# PCB_v1.net
KiCad netlist of a schematic drawn in EAGLE
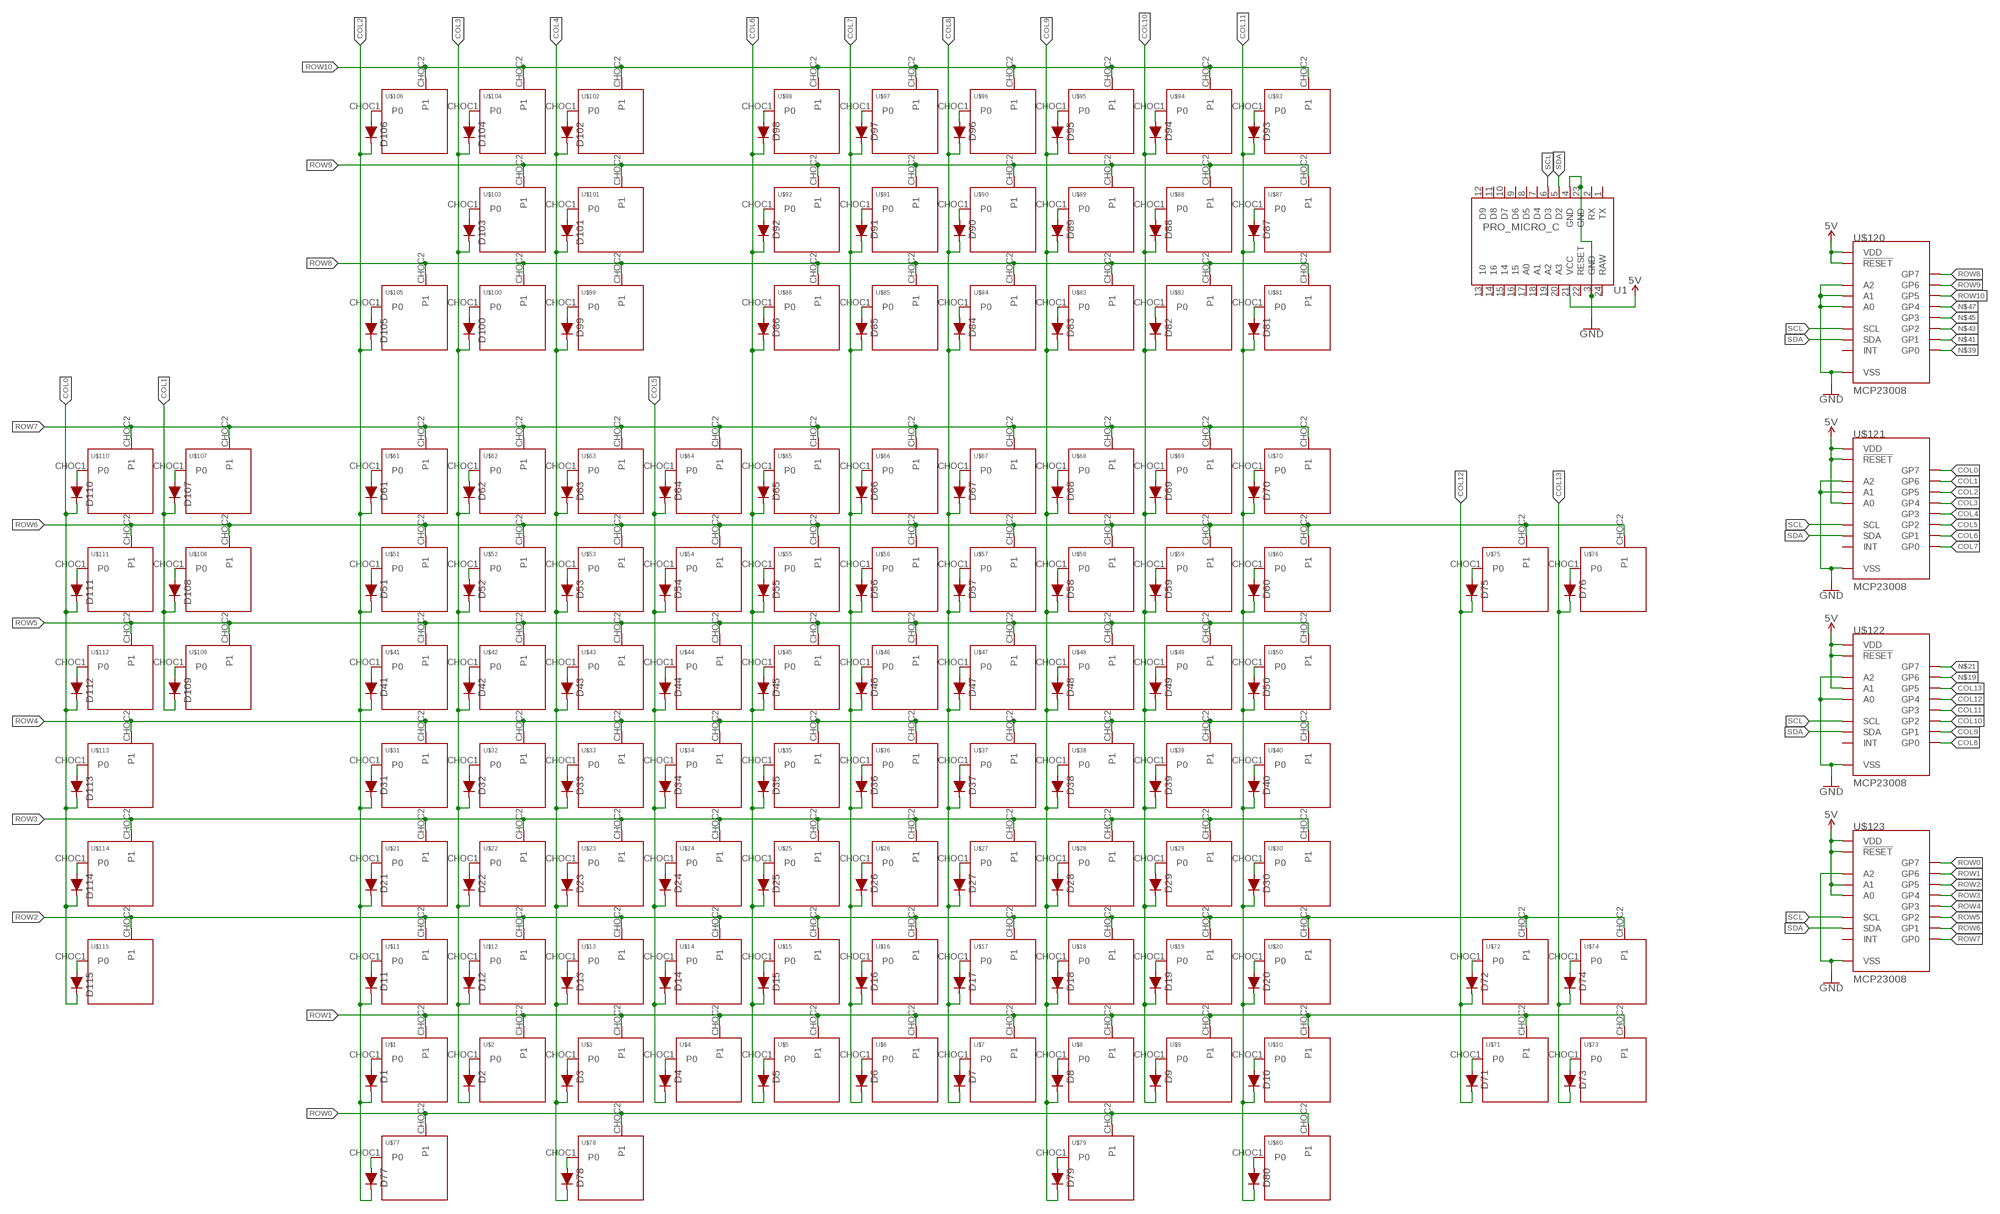
[diagram p0: schematic, sheet 1]

(export (version "E")
  (design (tool "Eeschema 10.0.6"))
  (components
    (comp (ref "D1")
      (value "200mA/100V/1V")
      (footprint "eagle-import:DIODE-1N4148-KIT")
      (libsource (lib "eagle-import") (part "DIODE-KIT"))
    )
    (comp (ref "D2")
      (value "200mA/100V/1V")
      (footprint "eagle-import:DIODE-1N4148-KIT")
      (libsource (lib "eagle-import") (part "DIODE-KIT"))
    )
    (comp (ref "D3")
      (value "200mA/100V/1V")
      (footprint "eagle-import:DIODE-1N4148-KIT")
      (libsource (lib "eagle-import") (part "DIODE-KIT"))
    )
    (comp (ref "D4")
      (value "200mA/100V/1V")
      (footprint "eagle-import:DIODE-1N4148-KIT")
      (libsource (lib "eagle-import") (part "DIODE-KIT"))
    )
    (comp (ref "D5")
      (value "200mA/100V/1V")
      (footprint "eagle-import:DIODE-1N4148-KIT")
      (libsource (lib "eagle-import") (part "DIODE-KIT"))
    )
    (comp (ref "D6")
      (value "200mA/100V/1V")
      (footprint "eagle-import:DIODE-1N4148-KIT")
      (libsource (lib "eagle-import") (part "DIODE-KIT"))
    )
    (comp (ref "D7")
      (value "200mA/100V/1V")
      (footprint "eagle-import:DIODE-1N4148-KIT")
      (libsource (lib "eagle-import") (part "DIODE-KIT"))
    )
    (comp (ref "D8")
      (value "200mA/100V/1V")
      (footprint "eagle-import:DIODE-1N4148-KIT")
      (libsource (lib "eagle-import") (part "DIODE-KIT"))
    )
    (comp (ref "D9")
      (value "200mA/100V/1V")
      (footprint "eagle-import:DIODE-1N4148-KIT")
      (libsource (lib "eagle-import") (part "DIODE-KIT"))
    )
    (comp (ref "D10")
      (value "200mA/100V/1V")
      (footprint "eagle-import:DIODE-1N4148-KIT")
      (libsource (lib "eagle-import") (part "DIODE-KIT"))
    )
    (comp (ref "D11")
      (value "200mA/100V/1V")
      (footprint "eagle-import:DIODE-1N4148-KIT")
      (libsource (lib "eagle-import") (part "DIODE-KIT"))
    )
    (comp (ref "D12")
      (value "200mA/100V/1V")
      (footprint "eagle-import:DIODE-1N4148-KIT")
      (libsource (lib "eagle-import") (part "DIODE-KIT"))
    )
    (comp (ref "D13")
      (value "200mA/100V/1V")
      (footprint "eagle-import:DIODE-1N4148-KIT")
      (libsource (lib "eagle-import") (part "DIODE-KIT"))
    )
    (comp (ref "D14")
      (value "200mA/100V/1V")
      (footprint "eagle-import:DIODE-1N4148-KIT")
      (libsource (lib "eagle-import") (part "DIODE-KIT"))
    )
    (comp (ref "D15")
      (value "200mA/100V/1V")
      (footprint "eagle-import:DIODE-1N4148-KIT")
      (libsource (lib "eagle-import") (part "DIODE-KIT"))
    )
    (comp (ref "D16")
      (value "200mA/100V/1V")
      (footprint "eagle-import:DIODE-1N4148-KIT")
      (libsource (lib "eagle-import") (part "DIODE-KIT"))
    )
    (comp (ref "D17")
      (value "200mA/100V/1V")
      (footprint "eagle-import:DIODE-1N4148-KIT")
      (libsource (lib "eagle-import") (part "DIODE-KIT"))
    )
    (comp (ref "D18")
      (value "200mA/100V/1V")
      (footprint "eagle-import:DIODE-1N4148-KIT")
      (libsource (lib "eagle-import") (part "DIODE-KIT"))
    )
    (comp (ref "D19")
      (value "200mA/100V/1V")
      (footprint "eagle-import:DIODE-1N4148-KIT")
      (libsource (lib "eagle-import") (part "DIODE-KIT"))
    )
    (comp (ref "D20")
      (value "200mA/100V/1V")
      (footprint "eagle-import:DIODE-1N4148-KIT")
      (libsource (lib "eagle-import") (part "DIODE-KIT"))
    )
    (comp (ref "D21")
      (value "200mA/100V/1V")
      (footprint "eagle-import:DIODE-1N4148-KIT")
      (libsource (lib "eagle-import") (part "DIODE-KIT"))
    )
    (comp (ref "D22")
      (value "200mA/100V/1V")
      (footprint "eagle-import:DIODE-1N4148-KIT")
      (libsource (lib "eagle-import") (part "DIODE-KIT"))
    )
    (comp (ref "D23")
      (value "200mA/100V/1V")
      (footprint "eagle-import:DIODE-1N4148-KIT")
      (libsource (lib "eagle-import") (part "DIODE-KIT"))
    )
    (comp (ref "D24")
      (value "200mA/100V/1V")
      (footprint "eagle-import:DIODE-1N4148-KIT")
      (libsource (lib "eagle-import") (part "DIODE-KIT"))
    )
    (comp (ref "D25")
      (value "200mA/100V/1V")
      (footprint "eagle-import:DIODE-1N4148-KIT")
      (libsource (lib "eagle-import") (part "DIODE-KIT"))
    )
    (comp (ref "D26")
      (value "200mA/100V/1V")
      (footprint "eagle-import:DIODE-1N4148-KIT")
      (libsource (lib "eagle-import") (part "DIODE-KIT"))
    )
    (comp (ref "D27")
      (value "200mA/100V/1V")
      (footprint "eagle-import:DIODE-1N4148-KIT")
      (libsource (lib "eagle-import") (part "DIODE-KIT"))
    )
    (comp (ref "D28")
      (value "200mA/100V/1V")
      (footprint "eagle-import:DIODE-1N4148-KIT")
      (libsource (lib "eagle-import") (part "DIODE-KIT"))
    )
    (comp (ref "D29")
      (value "200mA/100V/1V")
      (footprint "eagle-import:DIODE-1N4148-KIT")
      (libsource (lib "eagle-import") (part "DIODE-KIT"))
    )
    (comp (ref "D30")
      (value "200mA/100V/1V")
      (footprint "eagle-import:DIODE-1N4148-KIT")
      (libsource (lib "eagle-import") (part "DIODE-KIT"))
    )
    (comp (ref "D31")
      (value "200mA/100V/1V")
      (footprint "eagle-import:DIODE-1N4148-KIT")
      (libsource (lib "eagle-import") (part "DIODE-KIT"))
    )
    (comp (ref "D32")
      (value "200mA/100V/1V")
      (footprint "eagle-import:DIODE-1N4148-KIT")
      (libsource (lib "eagle-import") (part "DIODE-KIT"))
    )
    (comp (ref "D33")
      (value "200mA/100V/1V")
      (footprint "eagle-import:DIODE-1N4148-KIT")
      (libsource (lib "eagle-import") (part "DIODE-KIT"))
    )
    (comp (ref "D34")
      (value "200mA/100V/1V")
      (footprint "eagle-import:DIODE-1N4148-KIT")
      (libsource (lib "eagle-import") (part "DIODE-KIT"))
    )
    (comp (ref "D35")
      (value "200mA/100V/1V")
      (footprint "eagle-import:DIODE-1N4148-KIT")
      (libsource (lib "eagle-import") (part "DIODE-KIT"))
    )
    (comp (ref "D36")
      (value "200mA/100V/1V")
      (footprint "eagle-import:DIODE-1N4148-KIT")
      (libsource (lib "eagle-import") (part "DIODE-KIT"))
    )
    (comp (ref "D37")
      (value "200mA/100V/1V")
      (footprint "eagle-import:DIODE-1N4148-KIT")
      (libsource (lib "eagle-import") (part "DIODE-KIT"))
    )
    (comp (ref "D38")
      (value "200mA/100V/1V")
      (footprint "eagle-import:DIODE-1N4148-KIT")
      (libsource (lib "eagle-import") (part "DIODE-KIT"))
    )
    (comp (ref "D39")
      (value "200mA/100V/1V")
      (footprint "eagle-import:DIODE-1N4148-KIT")
      (libsource (lib "eagle-import") (part "DIODE-KIT"))
    )
    (comp (ref "D40")
      (value "200mA/100V/1V")
      (footprint "eagle-import:DIODE-1N4148-KIT")
      (libsource (lib "eagle-import") (part "DIODE-KIT"))
    )
    (comp (ref "D41")
      (value "200mA/100V/1V")
      (footprint "eagle-import:DIODE-1N4148-KIT")
      (libsource (lib "eagle-import") (part "DIODE-KIT"))
    )
    (comp (ref "D42")
      (value "200mA/100V/1V")
      (footprint "eagle-import:DIODE-1N4148-KIT")
      (libsource (lib "eagle-import") (part "DIODE-KIT"))
    )
    (comp (ref "D43")
      (value "200mA/100V/1V")
      (footprint "eagle-import:DIODE-1N4148-KIT")
      (libsource (lib "eagle-import") (part "DIODE-KIT"))
    )
    (comp (ref "D44")
      (value "200mA/100V/1V")
      (footprint "eagle-import:DIODE-1N4148-KIT")
      (libsource (lib "eagle-import") (part "DIODE-KIT"))
    )
    (comp (ref "D45")
      (value "200mA/100V/1V")
      (footprint "eagle-import:DIODE-1N4148-KIT")
      (libsource (lib "eagle-import") (part "DIODE-KIT"))
    )
    (comp (ref "D46")
      (value "200mA/100V/1V")
      (footprint "eagle-import:DIODE-1N4148-KIT")
      (libsource (lib "eagle-import") (part "DIODE-KIT"))
    )
    (comp (ref "D47")
      (value "200mA/100V/1V")
      (footprint "eagle-import:DIODE-1N4148-KIT")
      (libsource (lib "eagle-import") (part "DIODE-KIT"))
    )
    (comp (ref "D48")
      (value "200mA/100V/1V")
      (footprint "eagle-import:DIODE-1N4148-KIT")
      (libsource (lib "eagle-import") (part "DIODE-KIT"))
    )
    (comp (ref "D49")
      (value "200mA/100V/1V")
      (footprint "eagle-import:DIODE-1N4148-KIT")
      (libsource (lib "eagle-import") (part "DIODE-KIT"))
    )
    (comp (ref "D50")
      (value "200mA/100V/1V")
      (footprint "eagle-import:DIODE-1N4148-KIT")
      (libsource (lib "eagle-import") (part "DIODE-KIT"))
    )
    (comp (ref "D51")
      (value "200mA/100V/1V")
      (footprint "eagle-import:DIODE-1N4148-KIT")
      (libsource (lib "eagle-import") (part "DIODE-KIT"))
    )
    (comp (ref "D52")
      (value "200mA/100V/1V")
      (footprint "eagle-import:DIODE-1N4148-KIT")
      (libsource (lib "eagle-import") (part "DIODE-KIT"))
    )
    (comp (ref "D53")
      (value "200mA/100V/1V")
      (footprint "eagle-import:DIODE-1N4148-KIT")
      (libsource (lib "eagle-import") (part "DIODE-KIT"))
    )
    (comp (ref "D54")
      (value "200mA/100V/1V")
      (footprint "eagle-import:DIODE-1N4148-KIT")
      (libsource (lib "eagle-import") (part "DIODE-KIT"))
    )
    (comp (ref "D55")
      (value "200mA/100V/1V")
      (footprint "eagle-import:DIODE-1N4148-KIT")
      (libsource (lib "eagle-import") (part "DIODE-KIT"))
    )
    (comp (ref "D56")
      (value "200mA/100V/1V")
      (footprint "eagle-import:DIODE-1N4148-KIT")
      (libsource (lib "eagle-import") (part "DIODE-KIT"))
    )
    (comp (ref "D57")
      (value "200mA/100V/1V")
      (footprint "eagle-import:DIODE-1N4148-KIT")
      (libsource (lib "eagle-import") (part "DIODE-KIT"))
    )
    (comp (ref "D58")
      (value "200mA/100V/1V")
      (footprint "eagle-import:DIODE-1N4148-KIT")
      (libsource (lib "eagle-import") (part "DIODE-KIT"))
    )
    (comp (ref "D59")
      (value "200mA/100V/1V")
      (footprint "eagle-import:DIODE-1N4148-KIT")
      (libsource (lib "eagle-import") (part "DIODE-KIT"))
    )
    (comp (ref "D60")
      (value "200mA/100V/1V")
      (footprint "eagle-import:DIODE-1N4148-KIT")
      (libsource (lib "eagle-import") (part "DIODE-KIT"))
    )
    (comp (ref "D61")
      (value "200mA/100V/1V")
      (footprint "eagle-import:DIODE-1N4148-KIT")
      (libsource (lib "eagle-import") (part "DIODE-KIT"))
    )
    (comp (ref "D62")
      (value "200mA/100V/1V")
      (footprint "eagle-import:DIODE-1N4148-KIT")
      (libsource (lib "eagle-import") (part "DIODE-KIT"))
    )
    (comp (ref "D63")
      (value "200mA/100V/1V")
      (footprint "eagle-import:DIODE-1N4148-KIT")
      (libsource (lib "eagle-import") (part "DIODE-KIT"))
    )
    (comp (ref "D64")
      (value "200mA/100V/1V")
      (footprint "eagle-import:DIODE-1N4148-KIT")
      (libsource (lib "eagle-import") (part "DIODE-KIT"))
    )
    (comp (ref "D65")
      (value "200mA/100V/1V")
      (footprint "eagle-import:DIODE-1N4148-KIT")
      (libsource (lib "eagle-import") (part "DIODE-KIT"))
    )
    (comp (ref "D66")
      (value "200mA/100V/1V")
      (footprint "eagle-import:DIODE-1N4148-KIT")
      (libsource (lib "eagle-import") (part "DIODE-KIT"))
    )
    (comp (ref "D67")
      (value "200mA/100V/1V")
      (footprint "eagle-import:DIODE-1N4148-KIT")
      (libsource (lib "eagle-import") (part "DIODE-KIT"))
    )
    (comp (ref "D68")
      (value "200mA/100V/1V")
      (footprint "eagle-import:DIODE-1N4148-KIT")
      (libsource (lib "eagle-import") (part "DIODE-KIT"))
    )
    (comp (ref "D69")
      (value "200mA/100V/1V")
      (footprint "eagle-import:DIODE-1N4148-KIT")
      (libsource (lib "eagle-import") (part "DIODE-KIT"))
    )
    (comp (ref "D70")
      (value "200mA/100V/1V")
      (footprint "eagle-import:DIODE-1N4148-KIT")
      (libsource (lib "eagle-import") (part "DIODE-KIT"))
    )
    (comp (ref "D71")
      (value "200mA/100V/1V")
      (footprint "eagle-import:DIODE-1N4148-KIT")
      (libsource (lib "eagle-import") (part "DIODE-KIT"))
    )
    (comp (ref "D72")
      (value "200mA/100V/1V")
      (footprint "eagle-import:DIODE-1N4148-KIT")
      (libsource (lib "eagle-import") (part "DIODE-KIT"))
    )
    (comp (ref "D73")
      (value "200mA/100V/1V")
      (footprint "eagle-import:DIODE-1N4148-KIT")
      (libsource (lib "eagle-import") (part "DIODE-KIT"))
    )
    (comp (ref "D74")
      (value "200mA/100V/1V")
      (footprint "eagle-import:DIODE-1N4148-KIT")
      (libsource (lib "eagle-import") (part "DIODE-KIT"))
    )
    (comp (ref "D75")
      (value "200mA/100V/1V")
      (footprint "eagle-import:DIODE-1N4148-KIT")
      (libsource (lib "eagle-import") (part "DIODE-KIT"))
    )
    (comp (ref "D76")
      (value "200mA/100V/1V")
      (footprint "eagle-import:DIODE-1N4148-KIT")
      (libsource (lib "eagle-import") (part "DIODE-KIT"))
    )
    (comp (ref "D77")
      (value "200mA/100V/1V")
      (footprint "eagle-import:DIODE-1N4148-KIT")
      (libsource (lib "eagle-import") (part "DIODE-KIT"))
    )
    (comp (ref "D78")
      (value "200mA/100V/1V")
      (footprint "eagle-import:DIODE-1N4148-KIT")
      (libsource (lib "eagle-import") (part "DIODE-KIT"))
    )
    (comp (ref "D79")
      (value "200mA/100V/1V")
      (footprint "eagle-import:DIODE-1N4148-KIT")
      (libsource (lib "eagle-import") (part "DIODE-KIT"))
    )
    (comp (ref "D80")
      (value "200mA/100V/1V")
      (footprint "eagle-import:DIODE-1N4148-KIT")
      (libsource (lib "eagle-import") (part "DIODE-KIT"))
    )
    (comp (ref "D81")
      (value "200mA/100V/1V")
      (footprint "eagle-import:DIODE-1N4148-KIT")
      (libsource (lib "eagle-import") (part "DIODE-KIT"))
    )
    (comp (ref "D82")
      (value "200mA/100V/1V")
      (footprint "eagle-import:DIODE-1N4148-KIT")
      (libsource (lib "eagle-import") (part "DIODE-KIT"))
    )
    (comp (ref "D83")
      (value "200mA/100V/1V")
      (footprint "eagle-import:DIODE-1N4148-KIT")
      (libsource (lib "eagle-import") (part "DIODE-KIT"))
    )
    (comp (ref "D84")
      (value "200mA/100V/1V")
      (footprint "eagle-import:DIODE-1N4148-KIT")
      (libsource (lib "eagle-import") (part "DIODE-KIT"))
    )
    (comp (ref "D85")
      (value "200mA/100V/1V")
      (footprint "eagle-import:DIODE-1N4148-KIT")
      (libsource (lib "eagle-import") (part "DIODE-KIT"))
    )
    (comp (ref "D86")
      (value "200mA/100V/1V")
      (footprint "eagle-import:DIODE-1N4148-KIT")
      (libsource (lib "eagle-import") (part "DIODE-KIT"))
    )
    (comp (ref "D87")
      (value "200mA/100V/1V")
      (footprint "eagle-import:DIODE-1N4148-KIT")
      (libsource (lib "eagle-import") (part "DIODE-KIT"))
    )
    (comp (ref "D88")
      (value "200mA/100V/1V")
      (footprint "eagle-import:DIODE-1N4148-KIT")
      (libsource (lib "eagle-import") (part "DIODE-KIT"))
    )
    (comp (ref "D89")
      (value "200mA/100V/1V")
      (footprint "eagle-import:DIODE-1N4148-KIT")
      (libsource (lib "eagle-import") (part "DIODE-KIT"))
    )
    (comp (ref "D90")
      (value "200mA/100V/1V")
      (footprint "eagle-import:DIODE-1N4148-KIT")
      (libsource (lib "eagle-import") (part "DIODE-KIT"))
    )
    (comp (ref "D91")
      (value "200mA/100V/1V")
      (footprint "eagle-import:DIODE-1N4148-KIT")
      (libsource (lib "eagle-import") (part "DIODE-KIT"))
    )
    (comp (ref "D92")
      (value "200mA/100V/1V")
      (footprint "eagle-import:DIODE-1N4148-KIT")
      (libsource (lib "eagle-import") (part "DIODE-KIT"))
    )
    (comp (ref "D93")
      (value "200mA/100V/1V")
      (footprint "eagle-import:DIODE-1N4148-KIT")
      (libsource (lib "eagle-import") (part "DIODE-KIT"))
    )
    (comp (ref "D94")
      (value "200mA/100V/1V")
      (footprint "eagle-import:DIODE-1N4148-KIT")
      (libsource (lib "eagle-import") (part "DIODE-KIT"))
    )
    (comp (ref "D95")
      (value "200mA/100V/1V")
      (footprint "eagle-import:DIODE-1N4148-KIT")
      (libsource (lib "eagle-import") (part "DIODE-KIT"))
    )
    (comp (ref "D96")
      (value "200mA/100V/1V")
      (footprint "eagle-import:DIODE-1N4148-KIT")
      (libsource (lib "eagle-import") (part "DIODE-KIT"))
    )
    (comp (ref "D97")
      (value "200mA/100V/1V")
      (footprint "eagle-import:DIODE-1N4148-KIT")
      (libsource (lib "eagle-import") (part "DIODE-KIT"))
    )
    (comp (ref "D98")
      (value "200mA/100V/1V")
      (footprint "eagle-import:DIODE-1N4148-KIT")
      (libsource (lib "eagle-import") (part "DIODE-KIT"))
    )
    (comp (ref "D99")
      (value "200mA/100V/1V")
      (footprint "eagle-import:DIODE-1N4148-KIT")
      (libsource (lib "eagle-import") (part "DIODE-KIT"))
    )
    (comp (ref "D100")
      (value "200mA/100V/1V")
      (footprint "eagle-import:DIODE-1N4148-KIT")
      (libsource (lib "eagle-import") (part "DIODE-KIT"))
    )
    (comp (ref "D101")
      (value "200mA/100V/1V")
      (footprint "eagle-import:DIODE-1N4148-KIT")
      (libsource (lib "eagle-import") (part "DIODE-KIT"))
    )
    (comp (ref "D102")
      (value "200mA/100V/1V")
      (footprint "eagle-import:DIODE-1N4148-KIT")
      (libsource (lib "eagle-import") (part "DIODE-KIT"))
    )
    (comp (ref "D103")
      (value "200mA/100V/1V")
      (footprint "eagle-import:DIODE-1N4148-KIT")
      (libsource (lib "eagle-import") (part "DIODE-KIT"))
    )
    (comp (ref "D104")
      (value "200mA/100V/1V")
      (footprint "eagle-import:DIODE-1N4148-KIT")
      (libsource (lib "eagle-import") (part "DIODE-KIT"))
    )
    (comp (ref "D105")
      (value "200mA/100V/1V")
      (footprint "eagle-import:DIODE-1N4148-KIT")
      (libsource (lib "eagle-import") (part "DIODE-KIT"))
    )
    (comp (ref "D106")
      (value "200mA/100V/1V")
      (footprint "eagle-import:DIODE-1N4148-KIT")
      (libsource (lib "eagle-import") (part "DIODE-KIT"))
    )
    (comp (ref "D107")
      (value "200mA/100V/1V")
      (footprint "eagle-import:DIODE-1N4148-KIT")
      (libsource (lib "eagle-import") (part "DIODE-KIT"))
    )
    (comp (ref "D108")
      (value "200mA/100V/1V")
      (footprint "eagle-import:DIODE-1N4148-KIT")
      (libsource (lib "eagle-import") (part "DIODE-KIT"))
    )
    (comp (ref "D109")
      (value "200mA/100V/1V")
      (footprint "eagle-import:DIODE-1N4148-KIT")
      (libsource (lib "eagle-import") (part "DIODE-KIT"))
    )
    (comp (ref "D110")
      (value "200mA/100V/1V")
      (footprint "eagle-import:DIODE-1N4148-KIT")
      (libsource (lib "eagle-import") (part "DIODE-KIT"))
    )
    (comp (ref "D111")
      (value "200mA/100V/1V")
      (footprint "eagle-import:DIODE-1N4148-KIT")
      (libsource (lib "eagle-import") (part "DIODE-KIT"))
    )
    (comp (ref "D112")
      (value "200mA/100V/1V")
      (footprint "eagle-import:DIODE-1N4148-KIT")
      (libsource (lib "eagle-import") (part "DIODE-KIT"))
    )
    (comp (ref "D113")
      (value "200mA/100V/1V")
      (footprint "eagle-import:DIODE-1N4148-KIT")
      (libsource (lib "eagle-import") (part "DIODE-KIT"))
    )
    (comp (ref "D114")
      (value "200mA/100V/1V")
      (footprint "eagle-import:DIODE-1N4148-KIT")
      (libsource (lib "eagle-import") (part "DIODE-KIT"))
    )
    (comp (ref "D115")
      (value "200mA/100V/1V")
      (footprint "eagle-import:DIODE-1N4148-KIT")
      (libsource (lib "eagle-import") (part "DIODE-KIT"))
    )
    (comp (ref "U$1")
      (value "KEYSWITCH-PLAIN-CHOC-1U")
      (footprint "eagle-import:CHOC-1U")
      (libsource (lib "eagle-import") (part "KEYSWITCH-PLAIN-CHOC-1U"))
    )
    (comp (ref "U$2")
      (value "KEYSWITCH-PLAIN-CHOC-1U")
      (footprint "eagle-import:CHOC-1U")
      (libsource (lib "eagle-import") (part "KEYSWITCH-PLAIN-CHOC-1U"))
    )
    (comp (ref "U$3")
      (value "KEYSWITCH-PLAIN-CHOC-1U")
      (footprint "eagle-import:CHOC-1U")
      (libsource (lib "eagle-import") (part "KEYSWITCH-PLAIN-CHOC-1U"))
    )
    (comp (ref "U$4")
      (value "KEYSWITCH-PLAIN-CHOC-1U")
      (footprint "eagle-import:CHOC-1U")
      (libsource (lib "eagle-import") (part "KEYSWITCH-PLAIN-CHOC-1U"))
    )
    (comp (ref "U$5")
      (value "KEYSWITCH-PLAIN-CHOC-1U")
      (footprint "eagle-import:CHOC-1U")
      (libsource (lib "eagle-import") (part "KEYSWITCH-PLAIN-CHOC-1U"))
    )
    (comp (ref "U$6")
      (value "KEYSWITCH-PLAIN-CHOC-1U")
      (footprint "eagle-import:CHOC-1U")
      (libsource (lib "eagle-import") (part "KEYSWITCH-PLAIN-CHOC-1U"))
    )
    (comp (ref "U$7")
      (value "KEYSWITCH-PLAIN-CHOC-1U")
      (footprint "eagle-import:CHOC-1U")
      (libsource (lib "eagle-import") (part "KEYSWITCH-PLAIN-CHOC-1U"))
    )
    (comp (ref "U$8")
      (value "KEYSWITCH-PLAIN-CHOC-1U")
      (footprint "eagle-import:CHOC-1U")
      (libsource (lib "eagle-import") (part "KEYSWITCH-PLAIN-CHOC-1U"))
    )
    (comp (ref "U$9")
      (value "KEYSWITCH-PLAIN-CHOC-1U")
      (footprint "eagle-import:CHOC-1U")
      (libsource (lib "eagle-import") (part "KEYSWITCH-PLAIN-CHOC-1U"))
    )
    (comp (ref "U$10")
      (value "KEYSWITCH-PLAIN-CHOC-1U")
      (footprint "eagle-import:CHOC-1U")
      (libsource (lib "eagle-import") (part "KEYSWITCH-PLAIN-CHOC-1U"))
    )
    (comp (ref "U$11")
      (value "KEYSWITCH-PLAIN-CHOC-1U")
      (footprint "eagle-import:CHOC-1U")
      (libsource (lib "eagle-import") (part "KEYSWITCH-PLAIN-CHOC-1U"))
    )
    (comp (ref "U$12")
      (value "KEYSWITCH-PLAIN-CHOC-1U")
      (footprint "eagle-import:CHOC-1U")
      (libsource (lib "eagle-import") (part "KEYSWITCH-PLAIN-CHOC-1U"))
    )
    (comp (ref "U$13")
      (value "KEYSWITCH-PLAIN-CHOC-1U")
      (footprint "eagle-import:CHOC-1U")
      (libsource (lib "eagle-import") (part "KEYSWITCH-PLAIN-CHOC-1U"))
    )
    (comp (ref "U$14")
      (value "KEYSWITCH-PLAIN-CHOC-1U")
      (footprint "eagle-import:CHOC-1U")
      (libsource (lib "eagle-import") (part "KEYSWITCH-PLAIN-CHOC-1U"))
    )
    (comp (ref "U$15")
      (value "KEYSWITCH-PLAIN-CHOC-1U")
      (footprint "eagle-import:CHOC-1U")
      (libsource (lib "eagle-import") (part "KEYSWITCH-PLAIN-CHOC-1U"))
    )
    (comp (ref "U$16")
      (value "KEYSWITCH-PLAIN-CHOC-1U")
      (footprint "eagle-import:CHOC-1U")
      (libsource (lib "eagle-import") (part "KEYSWITCH-PLAIN-CHOC-1U"))
    )
    (comp (ref "U$17")
      (value "KEYSWITCH-PLAIN-CHOC-1U")
      (footprint "eagle-import:CHOC-1U")
      (libsource (lib "eagle-import") (part "KEYSWITCH-PLAIN-CHOC-1U"))
    )
    (comp (ref "U$18")
      (value "KEYSWITCH-PLAIN-CHOC-1U")
      (footprint "eagle-import:CHOC-1U")
      (libsource (lib "eagle-import") (part "KEYSWITCH-PLAIN-CHOC-1U"))
    )
    (comp (ref "U$19")
      (value "KEYSWITCH-PLAIN-CHOC-1U")
      (footprint "eagle-import:CHOC-1U")
      (libsource (lib "eagle-import") (part "KEYSWITCH-PLAIN-CHOC-1U"))
    )
    (comp (ref "U$20")
      (value "KEYSWITCH-PLAIN-CHOC-1U")
      (footprint "eagle-import:CHOC-1U")
      (libsource (lib "eagle-import") (part "KEYSWITCH-PLAIN-CHOC-1U"))
    )
    (comp (ref "U$21")
      (value "KEYSWITCH-PLAIN-CHOC-1U")
      (footprint "eagle-import:CHOC-1U")
      (libsource (lib "eagle-import") (part "KEYSWITCH-PLAIN-CHOC-1U"))
    )
    (comp (ref "U$22")
      (value "KEYSWITCH-PLAIN-CHOC-1U")
      (footprint "eagle-import:CHOC-1U")
      (libsource (lib "eagle-import") (part "KEYSWITCH-PLAIN-CHOC-1U"))
    )
    (comp (ref "U$23")
      (value "KEYSWITCH-PLAIN-CHOC-1U")
      (footprint "eagle-import:CHOC-1U")
      (libsource (lib "eagle-import") (part "KEYSWITCH-PLAIN-CHOC-1U"))
    )
    (comp (ref "U$24")
      (value "KEYSWITCH-PLAIN-CHOC-1U")
      (footprint "eagle-import:CHOC-1U")
      (libsource (lib "eagle-import") (part "KEYSWITCH-PLAIN-CHOC-1U"))
    )
    (comp (ref "U$25")
      (value "KEYSWITCH-PLAIN-CHOC-1U")
      (footprint "eagle-import:CHOC-1U")
      (libsource (lib "eagle-import") (part "KEYSWITCH-PLAIN-CHOC-1U"))
    )
    (comp (ref "U$26")
      (value "KEYSWITCH-PLAIN-CHOC-1U")
      (footprint "eagle-import:CHOC-1U")
      (libsource (lib "eagle-import") (part "KEYSWITCH-PLAIN-CHOC-1U"))
    )
    (comp (ref "U$27")
      (value "KEYSWITCH-PLAIN-CHOC-1U")
      (footprint "eagle-import:CHOC-1U")
      (libsource (lib "eagle-import") (part "KEYSWITCH-PLAIN-CHOC-1U"))
    )
    (comp (ref "U$28")
      (value "KEYSWITCH-PLAIN-CHOC-1U")
      (footprint "eagle-import:CHOC-1U")
      (libsource (lib "eagle-import") (part "KEYSWITCH-PLAIN-CHOC-1U"))
    )
    (comp (ref "U$29")
      (value "KEYSWITCH-PLAIN-CHOC-1U")
      (footprint "eagle-import:CHOC-1U")
      (libsource (lib "eagle-import") (part "KEYSWITCH-PLAIN-CHOC-1U"))
    )
    (comp (ref "U$30")
      (value "KEYSWITCH-PLAIN-CHOC-1U")
      (footprint "eagle-import:CHOC-1U")
      (libsource (lib "eagle-import") (part "KEYSWITCH-PLAIN-CHOC-1U"))
    )
    (comp (ref "U$31")
      (value "KEYSWITCH-PLAIN-CHOC-1U")
      (footprint "eagle-import:CHOC-1U")
      (libsource (lib "eagle-import") (part "KEYSWITCH-PLAIN-CHOC-1U"))
    )
    (comp (ref "U$32")
      (value "KEYSWITCH-PLAIN-CHOC-1U")
      (footprint "eagle-import:CHOC-1U")
      (libsource (lib "eagle-import") (part "KEYSWITCH-PLAIN-CHOC-1U"))
    )
    (comp (ref "U$33")
      (value "KEYSWITCH-PLAIN-CHOC-1U")
      (footprint "eagle-import:CHOC-1U")
      (libsource (lib "eagle-import") (part "KEYSWITCH-PLAIN-CHOC-1U"))
    )
    (comp (ref "U$34")
      (value "KEYSWITCH-PLAIN-CHOC-1U")
      (footprint "eagle-import:CHOC-1U")
      (libsource (lib "eagle-import") (part "KEYSWITCH-PLAIN-CHOC-1U"))
    )
    (comp (ref "U$35")
      (value "KEYSWITCH-PLAIN-CHOC-1U")
      (footprint "eagle-import:CHOC-1U")
      (libsource (lib "eagle-import") (part "KEYSWITCH-PLAIN-CHOC-1U"))
    )
    (comp (ref "U$36")
      (value "KEYSWITCH-PLAIN-CHOC-1U")
      (footprint "eagle-import:CHOC-1U")
      (libsource (lib "eagle-import") (part "KEYSWITCH-PLAIN-CHOC-1U"))
    )
    (comp (ref "U$37")
      (value "KEYSWITCH-PLAIN-CHOC-1U")
      (footprint "eagle-import:CHOC-1U")
      (libsource (lib "eagle-import") (part "KEYSWITCH-PLAIN-CHOC-1U"))
    )
    (comp (ref "U$38")
      (value "KEYSWITCH-PLAIN-CHOC-1U")
      (footprint "eagle-import:CHOC-1U")
      (libsource (lib "eagle-import") (part "KEYSWITCH-PLAIN-CHOC-1U"))
    )
    (comp (ref "U$39")
      (value "KEYSWITCH-PLAIN-CHOC-1U")
      (footprint "eagle-import:CHOC-1U")
      (libsource (lib "eagle-import") (part "KEYSWITCH-PLAIN-CHOC-1U"))
    )
    (comp (ref "U$40")
      (value "KEYSWITCH-PLAIN-CHOC-1U")
      (footprint "eagle-import:CHOC-1U")
      (libsource (lib "eagle-import") (part "KEYSWITCH-PLAIN-CHOC-1U"))
    )
    (comp (ref "U$41")
      (value "KEYSWITCH-PLAIN-CHOC-1U")
      (footprint "eagle-import:CHOC-1U")
      (libsource (lib "eagle-import") (part "KEYSWITCH-PLAIN-CHOC-1U"))
    )
    (comp (ref "U$42")
      (value "KEYSWITCH-PLAIN-CHOC-1U")
      (footprint "eagle-import:CHOC-1U")
      (libsource (lib "eagle-import") (part "KEYSWITCH-PLAIN-CHOC-1U"))
    )
    (comp (ref "U$43")
      (value "KEYSWITCH-PLAIN-CHOC-1U")
      (footprint "eagle-import:CHOC-1U")
      (libsource (lib "eagle-import") (part "KEYSWITCH-PLAIN-CHOC-1U"))
    )
    (comp (ref "U$44")
      (value "KEYSWITCH-PLAIN-CHOC-1U")
      (footprint "eagle-import:CHOC-1U")
      (libsource (lib "eagle-import") (part "KEYSWITCH-PLAIN-CHOC-1U"))
    )
    (comp (ref "U$45")
      (value "KEYSWITCH-PLAIN-CHOC-1U")
      (footprint "eagle-import:CHOC-1U")
      (libsource (lib "eagle-import") (part "KEYSWITCH-PLAIN-CHOC-1U"))
    )
    (comp (ref "U$46")
      (value "KEYSWITCH-PLAIN-CHOC-1U")
      (footprint "eagle-import:CHOC-1U")
      (libsource (lib "eagle-import") (part "KEYSWITCH-PLAIN-CHOC-1U"))
    )
    (comp (ref "U$47")
      (value "KEYSWITCH-PLAIN-CHOC-1U")
      (footprint "eagle-import:CHOC-1U")
      (libsource (lib "eagle-import") (part "KEYSWITCH-PLAIN-CHOC-1U"))
    )
    (comp (ref "U$48")
      (value "KEYSWITCH-PLAIN-CHOC-1U")
      (footprint "eagle-import:CHOC-1U")
      (libsource (lib "eagle-import") (part "KEYSWITCH-PLAIN-CHOC-1U"))
    )
    (comp (ref "U$49")
      (value "KEYSWITCH-PLAIN-CHOC-1U")
      (footprint "eagle-import:CHOC-1U")
      (libsource (lib "eagle-import") (part "KEYSWITCH-PLAIN-CHOC-1U"))
    )
    (comp (ref "U$50")
      (value "KEYSWITCH-PLAIN-CHOC-1U")
      (footprint "eagle-import:CHOC-1U")
      (libsource (lib "eagle-import") (part "KEYSWITCH-PLAIN-CHOC-1U"))
    )
    (comp (ref "U$51")
      (value "KEYSWITCH-PLAIN-CHOC-1U")
      (footprint "eagle-import:CHOC-1U")
      (libsource (lib "eagle-import") (part "KEYSWITCH-PLAIN-CHOC-1U"))
    )
    (comp (ref "U$52")
      (value "KEYSWITCH-PLAIN-CHOC-1U")
      (footprint "eagle-import:CHOC-1U")
      (libsource (lib "eagle-import") (part "KEYSWITCH-PLAIN-CHOC-1U"))
    )
    (comp (ref "U$53")
      (value "KEYSWITCH-PLAIN-CHOC-1U")
      (footprint "eagle-import:CHOC-1U")
      (libsource (lib "eagle-import") (part "KEYSWITCH-PLAIN-CHOC-1U"))
    )
    (comp (ref "U$54")
      (value "KEYSWITCH-PLAIN-CHOC-1U")
      (footprint "eagle-import:CHOC-1U")
      (libsource (lib "eagle-import") (part "KEYSWITCH-PLAIN-CHOC-1U"))
    )
    (comp (ref "U$55")
      (value "KEYSWITCH-PLAIN-CHOC-1U")
      (footprint "eagle-import:CHOC-1U")
      (libsource (lib "eagle-import") (part "KEYSWITCH-PLAIN-CHOC-1U"))
    )
    (comp (ref "U$56")
      (value "KEYSWITCH-PLAIN-CHOC-1U")
      (footprint "eagle-import:CHOC-1U")
      (libsource (lib "eagle-import") (part "KEYSWITCH-PLAIN-CHOC-1U"))
    )
    (comp (ref "U$57")
      (value "KEYSWITCH-PLAIN-CHOC-1U")
      (footprint "eagle-import:CHOC-1U")
      (libsource (lib "eagle-import") (part "KEYSWITCH-PLAIN-CHOC-1U"))
    )
    (comp (ref "U$58")
      (value "KEYSWITCH-PLAIN-CHOC-1U")
      (footprint "eagle-import:CHOC-1U")
      (libsource (lib "eagle-import") (part "KEYSWITCH-PLAIN-CHOC-1U"))
    )
    (comp (ref "U$59")
      (value "KEYSWITCH-PLAIN-CHOC-1U")
      (footprint "eagle-import:CHOC-1U")
      (libsource (lib "eagle-import") (part "KEYSWITCH-PLAIN-CHOC-1U"))
    )
    (comp (ref "U$60")
      (value "KEYSWITCH-PLAIN-CHOC-1U")
      (footprint "eagle-import:CHOC-1U")
      (libsource (lib "eagle-import") (part "KEYSWITCH-PLAIN-CHOC-1U"))
    )
    (comp (ref "U$61")
      (value "KEYSWITCH-PLAIN-CHOC-1U")
      (footprint "eagle-import:CHOC-1U")
      (libsource (lib "eagle-import") (part "KEYSWITCH-PLAIN-CHOC-1U"))
    )
    (comp (ref "U$62")
      (value "KEYSWITCH-PLAIN-CHOC-1U")
      (footprint "eagle-import:CHOC-1U")
      (libsource (lib "eagle-import") (part "KEYSWITCH-PLAIN-CHOC-1U"))
    )
    (comp (ref "U$63")
      (value "KEYSWITCH-PLAIN-CHOC-1U")
      (footprint "eagle-import:CHOC-1U")
      (libsource (lib "eagle-import") (part "KEYSWITCH-PLAIN-CHOC-1U"))
    )
    (comp (ref "U$64")
      (value "KEYSWITCH-PLAIN-CHOC-1U")
      (footprint "eagle-import:CHOC-1U")
      (libsource (lib "eagle-import") (part "KEYSWITCH-PLAIN-CHOC-1U"))
    )
    (comp (ref "U$65")
      (value "KEYSWITCH-PLAIN-CHOC-1U")
      (footprint "eagle-import:CHOC-1U")
      (libsource (lib "eagle-import") (part "KEYSWITCH-PLAIN-CHOC-1U"))
    )
    (comp (ref "U$66")
      (value "KEYSWITCH-PLAIN-CHOC-1U")
      (footprint "eagle-import:CHOC-1U")
      (libsource (lib "eagle-import") (part "KEYSWITCH-PLAIN-CHOC-1U"))
    )
    (comp (ref "U$67")
      (value "KEYSWITCH-PLAIN-CHOC-1U")
      (footprint "eagle-import:CHOC-1U")
      (libsource (lib "eagle-import") (part "KEYSWITCH-PLAIN-CHOC-1U"))
    )
    (comp (ref "U$68")
      (value "KEYSWITCH-PLAIN-CHOC-1U")
      (footprint "eagle-import:CHOC-1U")
      (libsource (lib "eagle-import") (part "KEYSWITCH-PLAIN-CHOC-1U"))
    )
    (comp (ref "U$69")
      (value "KEYSWITCH-PLAIN-CHOC-1U")
      (footprint "eagle-import:CHOC-1U")
      (libsource (lib "eagle-import") (part "KEYSWITCH-PLAIN-CHOC-1U"))
    )
    (comp (ref "U$70")
      (value "KEYSWITCH-PLAIN-CHOC-1U")
      (footprint "eagle-import:CHOC-1U")
      (libsource (lib "eagle-import") (part "KEYSWITCH-PLAIN-CHOC-1U"))
    )
    (comp (ref "U$71")
      (value "KEYSWITCH-PLAIN-CHOC-1U")
      (footprint "eagle-import:CHOC-1U")
      (libsource (lib "eagle-import") (part "KEYSWITCH-PLAIN-CHOC-1U"))
    )
    (comp (ref "U$72")
      (value "KEYSWITCH-PLAIN-CHOC-1U")
      (footprint "eagle-import:CHOC-1U")
      (libsource (lib "eagle-import") (part "KEYSWITCH-PLAIN-CHOC-1U"))
    )
    (comp (ref "U$73")
      (value "KEYSWITCH-PLAIN-CHOC-1U")
      (footprint "eagle-import:CHOC-1U")
      (libsource (lib "eagle-import") (part "KEYSWITCH-PLAIN-CHOC-1U"))
    )
    (comp (ref "U$74")
      (value "KEYSWITCH-PLAIN-CHOC-1U")
      (footprint "eagle-import:CHOC-1U")
      (libsource (lib "eagle-import") (part "KEYSWITCH-PLAIN-CHOC-1U"))
    )
    (comp (ref "U$75")
      (value "KEYSWITCH-PLAIN-CHOC-1U")
      (footprint "eagle-import:CHOC-1U")
      (libsource (lib "eagle-import") (part "KEYSWITCH-PLAIN-CHOC-1U"))
    )
    (comp (ref "U$76")
      (value "KEYSWITCH-PLAIN-CHOC-1U")
      (footprint "eagle-import:CHOC-1U")
      (libsource (lib "eagle-import") (part "KEYSWITCH-PLAIN-CHOC-1U"))
    )
    (comp (ref "U$77")
      (value "KEYSWITCH-PLAIN-CHOC-1U")
      (footprint "eagle-import:CHOC-1U")
      (libsource (lib "eagle-import") (part "KEYSWITCH-PLAIN-CHOC-1U"))
    )
    (comp (ref "U$78")
      (value "KEYSWITCH-PLAIN-CHOC-1U")
      (footprint "eagle-import:CHOC-1U")
      (libsource (lib "eagle-import") (part "KEYSWITCH-PLAIN-CHOC-1U"))
    )
    (comp (ref "U$79")
      (value "KEYSWITCH-PLAIN-CHOC-1U")
      (footprint "eagle-import:CHOC-1U")
      (libsource (lib "eagle-import") (part "KEYSWITCH-PLAIN-CHOC-1U"))
    )
    (comp (ref "U$80")
      (value "KEYSWITCH-PLAIN-CHOC-1U")
      (footprint "eagle-import:CHOC-1U")
      (libsource (lib "eagle-import") (part "KEYSWITCH-PLAIN-CHOC-1U"))
    )
    (comp (ref "U$81")
      (value "KEYSWITCH-PLAIN-CHOC-1U")
      (footprint "eagle-import:CHOC-1U")
      (libsource (lib "eagle-import") (part "KEYSWITCH-PLAIN-CHOC-1U"))
    )
    (comp (ref "U$82")
      (value "KEYSWITCH-PLAIN-CHOC-1U")
      (footprint "eagle-import:CHOC-1U")
      (libsource (lib "eagle-import") (part "KEYSWITCH-PLAIN-CHOC-1U"))
    )
    (comp (ref "U$83")
      (value "KEYSWITCH-PLAIN-CHOC-1U")
      (footprint "eagle-import:CHOC-1U")
      (libsource (lib "eagle-import") (part "KEYSWITCH-PLAIN-CHOC-1U"))
    )
    (comp (ref "U$84")
      (value "KEYSWITCH-PLAIN-CHOC-1U")
      (footprint "eagle-import:CHOC-1U")
      (libsource (lib "eagle-import") (part "KEYSWITCH-PLAIN-CHOC-1U"))
    )
    (comp (ref "U$85")
      (value "KEYSWITCH-PLAIN-CHOC-1U")
      (footprint "eagle-import:CHOC-1U")
      (libsource (lib "eagle-import") (part "KEYSWITCH-PLAIN-CHOC-1U"))
    )
    (comp (ref "U$86")
      (value "KEYSWITCH-PLAIN-CHOC-1U")
      (footprint "eagle-import:CHOC-1U")
      (libsource (lib "eagle-import") (part "KEYSWITCH-PLAIN-CHOC-1U"))
    )
    (comp (ref "U$87")
      (value "KEYSWITCH-PLAIN-CHOC-1U")
      (footprint "eagle-import:CHOC-1U")
      (libsource (lib "eagle-import") (part "KEYSWITCH-PLAIN-CHOC-1U"))
    )
    (comp (ref "U$88")
      (value "KEYSWITCH-PLAIN-CHOC-1U")
      (footprint "eagle-import:CHOC-1U")
      (libsource (lib "eagle-import") (part "KEYSWITCH-PLAIN-CHOC-1U"))
    )
    (comp (ref "U$89")
      (value "KEYSWITCH-PLAIN-CHOC-1U")
      (footprint "eagle-import:CHOC-1U")
      (libsource (lib "eagle-import") (part "KEYSWITCH-PLAIN-CHOC-1U"))
    )
    (comp (ref "U$90")
      (value "KEYSWITCH-PLAIN-CHOC-1U")
      (footprint "eagle-import:CHOC-1U")
      (libsource (lib "eagle-import") (part "KEYSWITCH-PLAIN-CHOC-1U"))
    )
    (comp (ref "U$91")
      (value "KEYSWITCH-PLAIN-CHOC-1U")
      (footprint "eagle-import:CHOC-1U")
      (libsource (lib "eagle-import") (part "KEYSWITCH-PLAIN-CHOC-1U"))
    )
    (comp (ref "U$92")
      (value "KEYSWITCH-PLAIN-CHOC-1U")
      (footprint "eagle-import:CHOC-1U")
      (libsource (lib "eagle-import") (part "KEYSWITCH-PLAIN-CHOC-1U"))
    )
    (comp (ref "U$93")
      (value "KEYSWITCH-PLAIN-CHOC-1U")
      (footprint "eagle-import:CHOC-1U")
      (libsource (lib "eagle-import") (part "KEYSWITCH-PLAIN-CHOC-1U"))
    )
    (comp (ref "U$94")
      (value "KEYSWITCH-PLAIN-CHOC-1U")
      (footprint "eagle-import:CHOC-1U")
      (libsource (lib "eagle-import") (part "KEYSWITCH-PLAIN-CHOC-1U"))
    )
    (comp (ref "U$95")
      (value "KEYSWITCH-PLAIN-CHOC-1U")
      (footprint "eagle-import:CHOC-1U")
      (libsource (lib "eagle-import") (part "KEYSWITCH-PLAIN-CHOC-1U"))
    )
    (comp (ref "U$96")
      (value "KEYSWITCH-PLAIN-CHOC-1U")
      (footprint "eagle-import:CHOC-1U")
      (libsource (lib "eagle-import") (part "KEYSWITCH-PLAIN-CHOC-1U"))
    )
    (comp (ref "U$97")
      (value "KEYSWITCH-PLAIN-CHOC-1U")
      (footprint "eagle-import:CHOC-1U")
      (libsource (lib "eagle-import") (part "KEYSWITCH-PLAIN-CHOC-1U"))
    )
    (comp (ref "U$98")
      (value "KEYSWITCH-PLAIN-CHOC-1U")
      (footprint "eagle-import:CHOC-1U")
      (libsource (lib "eagle-import") (part "KEYSWITCH-PLAIN-CHOC-1U"))
    )
    (comp (ref "U$99")
      (value "KEYSWITCH-PLAIN-CHOC-1U")
      (footprint "eagle-import:CHOC-1U")
      (libsource (lib "eagle-import") (part "KEYSWITCH-PLAIN-CHOC-1U"))
    )
    (comp (ref "U$100")
      (value "KEYSWITCH-PLAIN-CHOC-1U")
      (footprint "eagle-import:CHOC-1U")
      (libsource (lib "eagle-import") (part "KEYSWITCH-PLAIN-CHOC-1U"))
    )
    (comp (ref "U$101")
      (value "KEYSWITCH-PLAIN-CHOC-1U")
      (footprint "eagle-import:CHOC-1U")
      (libsource (lib "eagle-import") (part "KEYSWITCH-PLAIN-CHOC-1U"))
    )
    (comp (ref "U$102")
      (value "KEYSWITCH-PLAIN-CHOC-1U")
      (footprint "eagle-import:CHOC-1U")
      (libsource (lib "eagle-import") (part "KEYSWITCH-PLAIN-CHOC-1U"))
    )
    (comp (ref "U$103")
      (value "KEYSWITCH-PLAIN-CHOC-1U")
      (footprint "eagle-import:CHOC-1U")
      (libsource (lib "eagle-import") (part "KEYSWITCH-PLAIN-CHOC-1U"))
    )
    (comp (ref "U$104")
      (value "KEYSWITCH-PLAIN-CHOC-1U")
      (footprint "eagle-import:CHOC-1U")
      (libsource (lib "eagle-import") (part "KEYSWITCH-PLAIN-CHOC-1U"))
    )
    (comp (ref "U$105")
      (value "KEYSWITCH-PLAIN-CHOC-1U")
      (footprint "eagle-import:CHOC-1U")
      (libsource (lib "eagle-import") (part "KEYSWITCH-PLAIN-CHOC-1U"))
    )
    (comp (ref "U$106")
      (value "KEYSWITCH-PLAIN-CHOC-1U")
      (footprint "eagle-import:CHOC-1U")
      (libsource (lib "eagle-import") (part "KEYSWITCH-PLAIN-CHOC-1U"))
    )
    (comp (ref "U$107")
      (value "KEYSWITCH-PLAIN-CHOC-1U")
      (footprint "eagle-import:CHOC-1U")
      (libsource (lib "eagle-import") (part "KEYSWITCH-PLAIN-CHOC-1U"))
    )
    (comp (ref "U$108")
      (value "KEYSWITCH-PLAIN-CHOC-1U")
      (footprint "eagle-import:CHOC-1U")
      (libsource (lib "eagle-import") (part "KEYSWITCH-PLAIN-CHOC-1U"))
    )
    (comp (ref "U$109")
      (value "KEYSWITCH-PLAIN-CHOC-1U")
      (footprint "eagle-import:CHOC-1U")
      (libsource (lib "eagle-import") (part "KEYSWITCH-PLAIN-CHOC-1U"))
    )
    (comp (ref "U$110")
      (value "KEYSWITCH-PLAIN-CHOC-1U")
      (footprint "eagle-import:CHOC-1U")
      (libsource (lib "eagle-import") (part "KEYSWITCH-PLAIN-CHOC-1U"))
    )
    (comp (ref "U$111")
      (value "KEYSWITCH-PLAIN-CHOC-1U")
      (footprint "eagle-import:CHOC-1U")
      (libsource (lib "eagle-import") (part "KEYSWITCH-PLAIN-CHOC-1U"))
    )
    (comp (ref "U$112")
      (value "KEYSWITCH-PLAIN-CHOC-1U")
      (footprint "eagle-import:CHOC-1U")
      (libsource (lib "eagle-import") (part "KEYSWITCH-PLAIN-CHOC-1U"))
    )
    (comp (ref "U$113")
      (value "KEYSWITCH-PLAIN-CHOC-1U")
      (footprint "eagle-import:CHOC-1U")
      (libsource (lib "eagle-import") (part "KEYSWITCH-PLAIN-CHOC-1U"))
    )
    (comp (ref "U$114")
      (value "KEYSWITCH-PLAIN-CHOC-1U")
      (footprint "eagle-import:CHOC-1U")
      (libsource (lib "eagle-import") (part "KEYSWITCH-PLAIN-CHOC-1U"))
    )
    (comp (ref "U$115")
      (value "KEYSWITCH-PLAIN-CHOC-1U")
      (footprint "eagle-import:CHOC-1U")
      (libsource (lib "eagle-import") (part "KEYSWITCH-PLAIN-CHOC-1U"))
    )
    (comp (ref "U$120")
      (value "MCP23008")
      (footprint "eagle-import:DIP18")
      (libsource (lib "eagle-import") (part "MCP23008"))
    )
    (comp (ref "U$121")
      (value "MCP23008")
      (footprint "eagle-import:DIP18")
      (libsource (lib "eagle-import") (part "MCP23008"))
    )
    (comp (ref "U$122")
      (value "MCP23008")
      (footprint "eagle-import:DIP18")
      (libsource (lib "eagle-import") (part "MCP23008"))
    )
    (comp (ref "U$123")
      (value "MCP23008")
      (footprint "eagle-import:DIP18")
      (libsource (lib "eagle-import") (part "MCP23008"))
    )
    (comp (ref "U1")
      (value "PRO_MICRO_C")
      (footprint "eagle-import:PRO_MICRO_C")
      (libsource (lib "eagle-import") (part "PRO_MICRO_C"))
    )
  )
  (nets
    (net (code "1") (name "5V") (class "Default")
      (node (ref "U$120") (pin "18") (pinfunction "VDD_18") (pintype "bidirectional"))
      (node (ref "U$120") (pin "6") (pinfunction "~{RESET}_6") (pintype "bidirectional"))
      (node (ref "U$121") (pin "18") (pinfunction "VDD_18") (pintype "bidirectional"))
      (node (ref "U$121") (pin "5") (pinfunction "A0_5") (pintype "bidirectional"))
      (node (ref "U$121") (pin "6") (pinfunction "~{RESET}_6") (pintype "bidirectional"))
      (node (ref "U$122") (pin "18") (pinfunction "VDD_18") (pintype "bidirectional"))
      (node (ref "U$122") (pin "4") (pinfunction "A1_4") (pintype "bidirectional"))
      (node (ref "U$122") (pin "6") (pinfunction "~{RESET}_6") (pintype "bidirectional"))
      (node (ref "U$123") (pin "18") (pinfunction "VDD_18") (pintype "bidirectional"))
      (node (ref "U$123") (pin "4") (pinfunction "A1_4") (pintype "bidirectional"))
      (node (ref "U$123") (pin "5") (pinfunction "A0_5") (pintype "bidirectional"))
      (node (ref "U$123") (pin "6") (pinfunction "~{RESET}_6") (pintype "bidirectional"))
      (node (ref "U1") (pin "21") (pinfunction "VCC_21") (pintype "bidirectional"))
    )
    (net (code "2") (name "COL0") (class "Default")
      (node (ref "D110") (pin "C") (pinfunction "C_C") (pintype "passive"))
      (node (ref "D111") (pin "C") (pinfunction "C_C") (pintype "passive"))
      (node (ref "D112") (pin "C") (pinfunction "C_C") (pintype "passive"))
      (node (ref "D113") (pin "C") (pinfunction "C_C") (pintype "passive"))
      (node (ref "D114") (pin "C") (pinfunction "C_C") (pintype "passive"))
      (node (ref "D115") (pin "C") (pinfunction "C_C") (pintype "passive"))
      (node (ref "U$121") (pin "17") (pinfunction "GP7_17") (pintype "bidirectional"))
    )
    (net (code "3") (name "COL1") (class "Default")
      (node (ref "D107") (pin "C") (pinfunction "C_C") (pintype "passive"))
      (node (ref "D108") (pin "C") (pinfunction "C_C") (pintype "passive"))
      (node (ref "D109") (pin "C") (pinfunction "C_C") (pintype "passive"))
      (node (ref "U$121") (pin "16") (pinfunction "GP6_16") (pintype "bidirectional"))
    )
    (net (code "4") (name "COL2") (class "Default")
      (node (ref "D1") (pin "C") (pinfunction "C_C") (pintype "passive"))
      (node (ref "D105") (pin "C") (pinfunction "C_C") (pintype "passive"))
      (node (ref "D106") (pin "C") (pinfunction "C_C") (pintype "passive"))
      (node (ref "D11") (pin "C") (pinfunction "C_C") (pintype "passive"))
      (node (ref "D21") (pin "C") (pinfunction "C_C") (pintype "passive"))
      (node (ref "D31") (pin "C") (pinfunction "C_C") (pintype "passive"))
      (node (ref "D41") (pin "C") (pinfunction "C_C") (pintype "passive"))
      (node (ref "D51") (pin "C") (pinfunction "C_C") (pintype "passive"))
      (node (ref "D61") (pin "C") (pinfunction "C_C") (pintype "passive"))
      (node (ref "D77") (pin "C") (pinfunction "C_C") (pintype "passive"))
      (node (ref "U$121") (pin "15") (pinfunction "GP5_15") (pintype "bidirectional"))
    )
    (net (code "5") (name "COL3") (class "Default")
      (node (ref "D100") (pin "C") (pinfunction "C_C") (pintype "passive"))
      (node (ref "D103") (pin "C") (pinfunction "C_C") (pintype "passive"))
      (node (ref "D104") (pin "C") (pinfunction "C_C") (pintype "passive"))
      (node (ref "D12") (pin "C") (pinfunction "C_C") (pintype "passive"))
      (node (ref "D2") (pin "C") (pinfunction "C_C") (pintype "passive"))
      (node (ref "D22") (pin "C") (pinfunction "C_C") (pintype "passive"))
      (node (ref "D32") (pin "C") (pinfunction "C_C") (pintype "passive"))
      (node (ref "D42") (pin "C") (pinfunction "C_C") (pintype "passive"))
      (node (ref "D52") (pin "C") (pinfunction "C_C") (pintype "passive"))
      (node (ref "D62") (pin "C") (pinfunction "C_C") (pintype "passive"))
      (node (ref "U$121") (pin "14") (pinfunction "GP4_14") (pintype "bidirectional"))
    )
    (net (code "6") (name "COL4") (class "Default")
      (node (ref "D101") (pin "C") (pinfunction "C_C") (pintype "passive"))
      (node (ref "D102") (pin "C") (pinfunction "C_C") (pintype "passive"))
      (node (ref "D13") (pin "C") (pinfunction "C_C") (pintype "passive"))
      (node (ref "D23") (pin "C") (pinfunction "C_C") (pintype "passive"))
      (node (ref "D3") (pin "C") (pinfunction "C_C") (pintype "passive"))
      (node (ref "D33") (pin "C") (pinfunction "C_C") (pintype "passive"))
      (node (ref "D43") (pin "C") (pinfunction "C_C") (pintype "passive"))
      (node (ref "D53") (pin "C") (pinfunction "C_C") (pintype "passive"))
      (node (ref "D63") (pin "C") (pinfunction "C_C") (pintype "passive"))
      (node (ref "D78") (pin "C") (pinfunction "C_C") (pintype "passive"))
      (node (ref "D99") (pin "C") (pinfunction "C_C") (pintype "passive"))
      (node (ref "U$121") (pin "13") (pinfunction "GP3_13") (pintype "bidirectional"))
    )
    (net (code "7") (name "COL5") (class "Default")
      (node (ref "D14") (pin "C") (pinfunction "C_C") (pintype "passive"))
      (node (ref "D24") (pin "C") (pinfunction "C_C") (pintype "passive"))
      (node (ref "D34") (pin "C") (pinfunction "C_C") (pintype "passive"))
      (node (ref "D4") (pin "C") (pinfunction "C_C") (pintype "passive"))
      (node (ref "D44") (pin "C") (pinfunction "C_C") (pintype "passive"))
      (node (ref "D54") (pin "C") (pinfunction "C_C") (pintype "passive"))
      (node (ref "D64") (pin "C") (pinfunction "C_C") (pintype "passive"))
      (node (ref "U$121") (pin "12") (pinfunction "GP2_12") (pintype "bidirectional"))
    )
    (net (code "8") (name "COL6") (class "Default")
      (node (ref "D15") (pin "C") (pinfunction "C_C") (pintype "passive"))
      (node (ref "D25") (pin "C") (pinfunction "C_C") (pintype "passive"))
      (node (ref "D35") (pin "C") (pinfunction "C_C") (pintype "passive"))
      (node (ref "D45") (pin "C") (pinfunction "C_C") (pintype "passive"))
      (node (ref "D5") (pin "C") (pinfunction "C_C") (pintype "passive"))
      (node (ref "D55") (pin "C") (pinfunction "C_C") (pintype "passive"))
      (node (ref "D65") (pin "C") (pinfunction "C_C") (pintype "passive"))
      (node (ref "D86") (pin "C") (pinfunction "C_C") (pintype "passive"))
      (node (ref "D92") (pin "C") (pinfunction "C_C") (pintype "passive"))
      (node (ref "D98") (pin "C") (pinfunction "C_C") (pintype "passive"))
      (node (ref "U$121") (pin "11") (pinfunction "GP1_11") (pintype "bidirectional"))
    )
    (net (code "9") (name "COL7") (class "Default")
      (node (ref "D16") (pin "C") (pinfunction "C_C") (pintype "passive"))
      (node (ref "D26") (pin "C") (pinfunction "C_C") (pintype "passive"))
      (node (ref "D36") (pin "C") (pinfunction "C_C") (pintype "passive"))
      (node (ref "D46") (pin "C") (pinfunction "C_C") (pintype "passive"))
      (node (ref "D56") (pin "C") (pinfunction "C_C") (pintype "passive"))
      (node (ref "D6") (pin "C") (pinfunction "C_C") (pintype "passive"))
      (node (ref "D66") (pin "C") (pinfunction "C_C") (pintype "passive"))
      (node (ref "D85") (pin "C") (pinfunction "C_C") (pintype "passive"))
      (node (ref "D91") (pin "C") (pinfunction "C_C") (pintype "passive"))
      (node (ref "D97") (pin "C") (pinfunction "C_C") (pintype "passive"))
      (node (ref "U$121") (pin "10") (pinfunction "GP0_10") (pintype "bidirectional"))
    )
    (net (code "10") (name "COL8") (class "Default")
      (node (ref "D17") (pin "C") (pinfunction "C_C") (pintype "passive"))
      (node (ref "D27") (pin "C") (pinfunction "C_C") (pintype "passive"))
      (node (ref "D37") (pin "C") (pinfunction "C_C") (pintype "passive"))
      (node (ref "D47") (pin "C") (pinfunction "C_C") (pintype "passive"))
      (node (ref "D57") (pin "C") (pinfunction "C_C") (pintype "passive"))
      (node (ref "D67") (pin "C") (pinfunction "C_C") (pintype "passive"))
      (node (ref "D7") (pin "C") (pinfunction "C_C") (pintype "passive"))
      (node (ref "D84") (pin "C") (pinfunction "C_C") (pintype "passive"))
      (node (ref "D90") (pin "C") (pinfunction "C_C") (pintype "passive"))
      (node (ref "D96") (pin "C") (pinfunction "C_C") (pintype "passive"))
      (node (ref "U$122") (pin "10") (pinfunction "GP0_10") (pintype "bidirectional"))
    )
    (net (code "11") (name "COL9") (class "Default")
      (node (ref "D18") (pin "C") (pinfunction "C_C") (pintype "passive"))
      (node (ref "D28") (pin "C") (pinfunction "C_C") (pintype "passive"))
      (node (ref "D38") (pin "C") (pinfunction "C_C") (pintype "passive"))
      (node (ref "D48") (pin "C") (pinfunction "C_C") (pintype "passive"))
      (node (ref "D58") (pin "C") (pinfunction "C_C") (pintype "passive"))
      (node (ref "D68") (pin "C") (pinfunction "C_C") (pintype "passive"))
      (node (ref "D79") (pin "C") (pinfunction "C_C") (pintype "passive"))
      (node (ref "D8") (pin "C") (pinfunction "C_C") (pintype "passive"))
      (node (ref "D83") (pin "C") (pinfunction "C_C") (pintype "passive"))
      (node (ref "D89") (pin "C") (pinfunction "C_C") (pintype "passive"))
      (node (ref "D95") (pin "C") (pinfunction "C_C") (pintype "passive"))
      (node (ref "U$122") (pin "11") (pinfunction "GP1_11") (pintype "bidirectional"))
    )
    (net (code "12") (name "COL10") (class "Default")
      (node (ref "D19") (pin "C") (pinfunction "C_C") (pintype "passive"))
      (node (ref "D29") (pin "C") (pinfunction "C_C") (pintype "passive"))
      (node (ref "D39") (pin "C") (pinfunction "C_C") (pintype "passive"))
      (node (ref "D49") (pin "C") (pinfunction "C_C") (pintype "passive"))
      (node (ref "D59") (pin "C") (pinfunction "C_C") (pintype "passive"))
      (node (ref "D69") (pin "C") (pinfunction "C_C") (pintype "passive"))
      (node (ref "D82") (pin "C") (pinfunction "C_C") (pintype "passive"))
      (node (ref "D88") (pin "C") (pinfunction "C_C") (pintype "passive"))
      (node (ref "D9") (pin "C") (pinfunction "C_C") (pintype "passive"))
      (node (ref "D94") (pin "C") (pinfunction "C_C") (pintype "passive"))
      (node (ref "U$122") (pin "12") (pinfunction "GP2_12") (pintype "bidirectional"))
    )
    (net (code "13") (name "COL11") (class "Default")
      (node (ref "D10") (pin "C") (pinfunction "C_C") (pintype "passive"))
      (node (ref "D20") (pin "C") (pinfunction "C_C") (pintype "passive"))
      (node (ref "D30") (pin "C") (pinfunction "C_C") (pintype "passive"))
      (node (ref "D40") (pin "C") (pinfunction "C_C") (pintype "passive"))
      (node (ref "D50") (pin "C") (pinfunction "C_C") (pintype "passive"))
      (node (ref "D60") (pin "C") (pinfunction "C_C") (pintype "passive"))
      (node (ref "D70") (pin "C") (pinfunction "C_C") (pintype "passive"))
      (node (ref "D80") (pin "C") (pinfunction "C_C") (pintype "passive"))
      (node (ref "D81") (pin "C") (pinfunction "C_C") (pintype "passive"))
      (node (ref "D87") (pin "C") (pinfunction "C_C") (pintype "passive"))
      (node (ref "D93") (pin "C") (pinfunction "C_C") (pintype "passive"))
      (node (ref "U$122") (pin "13") (pinfunction "GP3_13") (pintype "bidirectional"))
    )
    (net (code "14") (name "COL12") (class "Default")
      (node (ref "D71") (pin "C") (pinfunction "C_C") (pintype "passive"))
      (node (ref "D72") (pin "C") (pinfunction "C_C") (pintype "passive"))
      (node (ref "D75") (pin "C") (pinfunction "C_C") (pintype "passive"))
      (node (ref "U$122") (pin "14") (pinfunction "GP4_14") (pintype "bidirectional"))
    )
    (net (code "15") (name "COL13") (class "Default")
      (node (ref "D73") (pin "C") (pinfunction "C_C") (pintype "passive"))
      (node (ref "D74") (pin "C") (pinfunction "C_C") (pintype "passive"))
      (node (ref "D76") (pin "C") (pinfunction "C_C") (pintype "passive"))
      (node (ref "U$122") (pin "15") (pinfunction "GP5_15") (pintype "bidirectional"))
    )
    (net (code "16") (name "GND") (class "Default")
      (node (ref "U$120") (pin "3") (pinfunction "A2_3") (pintype "bidirectional"))
      (node (ref "U$120") (pin "4") (pinfunction "A1_4") (pintype "bidirectional"))
      (node (ref "U$120") (pin "5") (pinfunction "A0_5") (pintype "bidirectional"))
      (node (ref "U$120") (pin "9") (pinfunction "VSS_9") (pintype "bidirectional"))
      (node (ref "U$121") (pin "3") (pinfunction "A2_3") (pintype "bidirectional"))
      (node (ref "U$121") (pin "4") (pinfunction "A1_4") (pintype "bidirectional"))
      (node (ref "U$121") (pin "9") (pinfunction "VSS_9") (pintype "bidirectional"))
      (node (ref "U$122") (pin "3") (pinfunction "A2_3") (pintype "bidirectional"))
      (node (ref "U$122") (pin "5") (pinfunction "A0_5") (pintype "bidirectional"))
      (node (ref "U$122") (pin "9") (pinfunction "VSS_9") (pintype "bidirectional"))
      (node (ref "U$123") (pin "3") (pinfunction "A2_3") (pintype "bidirectional"))
      (node (ref "U$123") (pin "9") (pinfunction "VSS_9") (pintype "bidirectional"))
      (node (ref "U1") (pin "23") (pinfunction "GND_23") (pintype "bidirectional"))
      (node (ref "U1") (pin "3") (pinfunction "GND_3") (pintype "bidirectional"))
      (node (ref "U1") (pin "4") (pinfunction "GND_4") (pintype "bidirectional"))
    )
    (net (code "17") (name "N$19") (class "Default")
      (node (ref "U$122") (pin "16") (pinfunction "GP6_16") (pintype "bidirectional"))
    )
    (net (code "18") (name "N$21") (class "Default")
      (node (ref "U$122") (pin "17") (pinfunction "GP7_17") (pintype "bidirectional"))
    )
    (net (code "19") (name "N$39") (class "Default")
      (node (ref "U$120") (pin "10") (pinfunction "GP0_10") (pintype "bidirectional"))
    )
    (net (code "20") (name "N$41") (class "Default")
      (node (ref "U$120") (pin "11") (pinfunction "GP1_11") (pintype "bidirectional"))
    )
    (net (code "21") (name "N$43") (class "Default")
      (node (ref "U$120") (pin "12") (pinfunction "GP2_12") (pintype "bidirectional"))
    )
    (net (code "22") (name "N$45") (class "Default")
      (node (ref "U$120") (pin "13") (pinfunction "GP3_13") (pintype "bidirectional"))
    )
    (net (code "23") (name "N$47") (class "Default")
      (node (ref "U$120") (pin "14") (pinfunction "GP4_14") (pintype "bidirectional"))
    )
    (net (code "24") (name "Net-(U$1-P0)") (class "Default")
      (node (ref "D1") (pin "A") (pinfunction "A_A") (pintype "passive"))
      (node (ref "U$1") (pin "CHOC1") (pinfunction "P0_CHOC1") (pintype "bidirectional"))
    )
    (net (code "25") (name "Net-(U$2-P0)") (class "Default")
      (node (ref "D2") (pin "A") (pinfunction "A_A") (pintype "passive"))
      (node (ref "U$2") (pin "CHOC1") (pinfunction "P0_CHOC1") (pintype "bidirectional"))
    )
    (net (code "26") (name "Net-(U$3-P0)") (class "Default")
      (node (ref "D3") (pin "A") (pinfunction "A_A") (pintype "passive"))
      (node (ref "U$3") (pin "CHOC1") (pinfunction "P0_CHOC1") (pintype "bidirectional"))
    )
    (net (code "27") (name "Net-(U$4-P0)") (class "Default")
      (node (ref "D4") (pin "A") (pinfunction "A_A") (pintype "passive"))
      (node (ref "U$4") (pin "CHOC1") (pinfunction "P0_CHOC1") (pintype "bidirectional"))
    )
    (net (code "28") (name "Net-(U$5-P0)") (class "Default")
      (node (ref "D5") (pin "A") (pinfunction "A_A") (pintype "passive"))
      (node (ref "U$5") (pin "CHOC1") (pinfunction "P0_CHOC1") (pintype "bidirectional"))
    )
    (net (code "29") (name "Net-(U$6-P0)") (class "Default")
      (node (ref "D6") (pin "A") (pinfunction "A_A") (pintype "passive"))
      (node (ref "U$6") (pin "CHOC1") (pinfunction "P0_CHOC1") (pintype "bidirectional"))
    )
    (net (code "30") (name "Net-(U$7-P0)") (class "Default")
      (node (ref "D7") (pin "A") (pinfunction "A_A") (pintype "passive"))
      (node (ref "U$7") (pin "CHOC1") (pinfunction "P0_CHOC1") (pintype "bidirectional"))
    )
    (net (code "31") (name "Net-(U$8-P0)") (class "Default")
      (node (ref "D8") (pin "A") (pinfunction "A_A") (pintype "passive"))
      (node (ref "U$8") (pin "CHOC1") (pinfunction "P0_CHOC1") (pintype "bidirectional"))
    )
    (net (code "32") (name "Net-(U$9-P0)") (class "Default")
      (node (ref "D9") (pin "A") (pinfunction "A_A") (pintype "passive"))
      (node (ref "U$9") (pin "CHOC1") (pinfunction "P0_CHOC1") (pintype "bidirectional"))
    )
    (net (code "33") (name "Net-(U$10-P0)") (class "Default")
      (node (ref "D10") (pin "A") (pinfunction "A_A") (pintype "passive"))
      (node (ref "U$10") (pin "CHOC1") (pinfunction "P0_CHOC1") (pintype "bidirectional"))
    )
    (net (code "34") (name "Net-(U$11-P0)") (class "Default")
      (node (ref "D11") (pin "A") (pinfunction "A_A") (pintype "passive"))
      (node (ref "U$11") (pin "CHOC1") (pinfunction "P0_CHOC1") (pintype "bidirectional"))
    )
    (net (code "35") (name "Net-(U$12-P0)") (class "Default")
      (node (ref "D12") (pin "A") (pinfunction "A_A") (pintype "passive"))
      (node (ref "U$12") (pin "CHOC1") (pinfunction "P0_CHOC1") (pintype "bidirectional"))
    )
    (net (code "36") (name "Net-(U$13-P0)") (class "Default")
      (node (ref "D13") (pin "A") (pinfunction "A_A") (pintype "passive"))
      (node (ref "U$13") (pin "CHOC1") (pinfunction "P0_CHOC1") (pintype "bidirectional"))
    )
    (net (code "37") (name "Net-(U$14-P0)") (class "Default")
      (node (ref "D14") (pin "A") (pinfunction "A_A") (pintype "passive"))
      (node (ref "U$14") (pin "CHOC1") (pinfunction "P0_CHOC1") (pintype "bidirectional"))
    )
    (net (code "38") (name "Net-(U$15-P0)") (class "Default")
      (node (ref "D15") (pin "A") (pinfunction "A_A") (pintype "passive"))
      (node (ref "U$15") (pin "CHOC1") (pinfunction "P0_CHOC1") (pintype "bidirectional"))
    )
    (net (code "39") (name "Net-(U$16-P0)") (class "Default")
      (node (ref "D16") (pin "A") (pinfunction "A_A") (pintype "passive"))
      (node (ref "U$16") (pin "CHOC1") (pinfunction "P0_CHOC1") (pintype "bidirectional"))
    )
    (net (code "40") (name "Net-(U$17-P0)") (class "Default")
      (node (ref "D17") (pin "A") (pinfunction "A_A") (pintype "passive"))
      (node (ref "U$17") (pin "CHOC1") (pinfunction "P0_CHOC1") (pintype "bidirectional"))
    )
    (net (code "41") (name "Net-(U$18-P0)") (class "Default")
      (node (ref "D18") (pin "A") (pinfunction "A_A") (pintype "passive"))
      (node (ref "U$18") (pin "CHOC1") (pinfunction "P0_CHOC1") (pintype "bidirectional"))
    )
    (net (code "42") (name "Net-(U$19-P0)") (class "Default")
      (node (ref "D19") (pin "A") (pinfunction "A_A") (pintype "passive"))
      (node (ref "U$19") (pin "CHOC1") (pinfunction "P0_CHOC1") (pintype "bidirectional"))
    )
    (net (code "43") (name "Net-(U$20-P0)") (class "Default")
      (node (ref "D20") (pin "A") (pinfunction "A_A") (pintype "passive"))
      (node (ref "U$20") (pin "CHOC1") (pinfunction "P0_CHOC1") (pintype "bidirectional"))
    )
    (net (code "44") (name "Net-(U$21-P0)") (class "Default")
      (node (ref "D21") (pin "A") (pinfunction "A_A") (pintype "passive"))
      (node (ref "U$21") (pin "CHOC1") (pinfunction "P0_CHOC1") (pintype "bidirectional"))
    )
    (net (code "45") (name "Net-(U$22-P0)") (class "Default")
      (node (ref "D22") (pin "A") (pinfunction "A_A") (pintype "passive"))
      (node (ref "U$22") (pin "CHOC1") (pinfunction "P0_CHOC1") (pintype "bidirectional"))
    )
    (net (code "46") (name "Net-(U$23-P0)") (class "Default")
      (node (ref "D23") (pin "A") (pinfunction "A_A") (pintype "passive"))
      (node (ref "U$23") (pin "CHOC1") (pinfunction "P0_CHOC1") (pintype "bidirectional"))
    )
    (net (code "47") (name "Net-(U$24-P0)") (class "Default")
      (node (ref "D24") (pin "A") (pinfunction "A_A") (pintype "passive"))
      (node (ref "U$24") (pin "CHOC1") (pinfunction "P0_CHOC1") (pintype "bidirectional"))
    )
    (net (code "48") (name "Net-(U$25-P0)") (class "Default")
      (node (ref "D25") (pin "A") (pinfunction "A_A") (pintype "passive"))
      (node (ref "U$25") (pin "CHOC1") (pinfunction "P0_CHOC1") (pintype "bidirectional"))
    )
    (net (code "49") (name "Net-(U$26-P0)") (class "Default")
      (node (ref "D26") (pin "A") (pinfunction "A_A") (pintype "passive"))
      (node (ref "U$26") (pin "CHOC1") (pinfunction "P0_CHOC1") (pintype "bidirectional"))
    )
    (net (code "50") (name "Net-(U$27-P0)") (class "Default")
      (node (ref "D27") (pin "A") (pinfunction "A_A") (pintype "passive"))
      (node (ref "U$27") (pin "CHOC1") (pinfunction "P0_CHOC1") (pintype "bidirectional"))
    )
    (net (code "51") (name "Net-(U$28-P0)") (class "Default")
      (node (ref "D28") (pin "A") (pinfunction "A_A") (pintype "passive"))
      (node (ref "U$28") (pin "CHOC1") (pinfunction "P0_CHOC1") (pintype "bidirectional"))
    )
    (net (code "52") (name "Net-(U$29-P0)") (class "Default")
      (node (ref "D29") (pin "A") (pinfunction "A_A") (pintype "passive"))
      (node (ref "U$29") (pin "CHOC1") (pinfunction "P0_CHOC1") (pintype "bidirectional"))
    )
    (net (code "53") (name "Net-(U$30-P0)") (class "Default")
      (node (ref "D30") (pin "A") (pinfunction "A_A") (pintype "passive"))
      (node (ref "U$30") (pin "CHOC1") (pinfunction "P0_CHOC1") (pintype "bidirectional"))
    )
    (net (code "54") (name "Net-(U$31-P0)") (class "Default")
      (node (ref "D31") (pin "A") (pinfunction "A_A") (pintype "passive"))
      (node (ref "U$31") (pin "CHOC1") (pinfunction "P0_CHOC1") (pintype "bidirectional"))
    )
    (net (code "55") (name "Net-(U$32-P0)") (class "Default")
      (node (ref "D32") (pin "A") (pinfunction "A_A") (pintype "passive"))
      (node (ref "U$32") (pin "CHOC1") (pinfunction "P0_CHOC1") (pintype "bidirectional"))
    )
    (net (code "56") (name "Net-(U$33-P0)") (class "Default")
      (node (ref "D33") (pin "A") (pinfunction "A_A") (pintype "passive"))
      (node (ref "U$33") (pin "CHOC1") (pinfunction "P0_CHOC1") (pintype "bidirectional"))
    )
    (net (code "57") (name "Net-(U$34-P0)") (class "Default")
      (node (ref "D34") (pin "A") (pinfunction "A_A") (pintype "passive"))
      (node (ref "U$34") (pin "CHOC1") (pinfunction "P0_CHOC1") (pintype "bidirectional"))
    )
    (net (code "58") (name "Net-(U$35-P0)") (class "Default")
      (node (ref "D35") (pin "A") (pinfunction "A_A") (pintype "passive"))
      (node (ref "U$35") (pin "CHOC1") (pinfunction "P0_CHOC1") (pintype "bidirectional"))
    )
    (net (code "59") (name "Net-(U$36-P0)") (class "Default")
      (node (ref "D36") (pin "A") (pinfunction "A_A") (pintype "passive"))
      (node (ref "U$36") (pin "CHOC1") (pinfunction "P0_CHOC1") (pintype "bidirectional"))
    )
    (net (code "60") (name "Net-(U$37-P0)") (class "Default")
      (node (ref "D37") (pin "A") (pinfunction "A_A") (pintype "passive"))
      (node (ref "U$37") (pin "CHOC1") (pinfunction "P0_CHOC1") (pintype "bidirectional"))
    )
    (net (code "61") (name "Net-(U$38-P0)") (class "Default")
      (node (ref "D38") (pin "A") (pinfunction "A_A") (pintype "passive"))
      (node (ref "U$38") (pin "CHOC1") (pinfunction "P0_CHOC1") (pintype "bidirectional"))
    )
    (net (code "62") (name "Net-(U$39-P0)") (class "Default")
      (node (ref "D39") (pin "A") (pinfunction "A_A") (pintype "passive"))
      (node (ref "U$39") (pin "CHOC1") (pinfunction "P0_CHOC1") (pintype "bidirectional"))
    )
    (net (code "63") (name "Net-(U$40-P0)") (class "Default")
      (node (ref "D40") (pin "A") (pinfunction "A_A") (pintype "passive"))
      (node (ref "U$40") (pin "CHOC1") (pinfunction "P0_CHOC1") (pintype "bidirectional"))
    )
    (net (code "64") (name "Net-(U$41-P0)") (class "Default")
      (node (ref "D41") (pin "A") (pinfunction "A_A") (pintype "passive"))
      (node (ref "U$41") (pin "CHOC1") (pinfunction "P0_CHOC1") (pintype "bidirectional"))
    )
    (net (code "65") (name "Net-(U$42-P0)") (class "Default")
      (node (ref "D42") (pin "A") (pinfunction "A_A") (pintype "passive"))
      (node (ref "U$42") (pin "CHOC1") (pinfunction "P0_CHOC1") (pintype "bidirectional"))
    )
    (net (code "66") (name "Net-(U$43-P0)") (class "Default")
      (node (ref "D43") (pin "A") (pinfunction "A_A") (pintype "passive"))
      (node (ref "U$43") (pin "CHOC1") (pinfunction "P0_CHOC1") (pintype "bidirectional"))
    )
    (net (code "67") (name "Net-(U$44-P0)") (class "Default")
      (node (ref "D44") (pin "A") (pinfunction "A_A") (pintype "passive"))
      (node (ref "U$44") (pin "CHOC1") (pinfunction "P0_CHOC1") (pintype "bidirectional"))
    )
    (net (code "68") (name "Net-(U$45-P0)") (class "Default")
      (node (ref "D45") (pin "A") (pinfunction "A_A") (pintype "passive"))
      (node (ref "U$45") (pin "CHOC1") (pinfunction "P0_CHOC1") (pintype "bidirectional"))
    )
    (net (code "69") (name "Net-(U$46-P0)") (class "Default")
      (node (ref "D46") (pin "A") (pinfunction "A_A") (pintype "passive"))
      (node (ref "U$46") (pin "CHOC1") (pinfunction "P0_CHOC1") (pintype "bidirectional"))
    )
    (net (code "70") (name "Net-(U$47-P0)") (class "Default")
      (node (ref "D47") (pin "A") (pinfunction "A_A") (pintype "passive"))
      (node (ref "U$47") (pin "CHOC1") (pinfunction "P0_CHOC1") (pintype "bidirectional"))
    )
    (net (code "71") (name "Net-(U$48-P0)") (class "Default")
      (node (ref "D48") (pin "A") (pinfunction "A_A") (pintype "passive"))
      (node (ref "U$48") (pin "CHOC1") (pinfunction "P0_CHOC1") (pintype "bidirectional"))
    )
    (net (code "72") (name "Net-(U$49-P0)") (class "Default")
      (node (ref "D49") (pin "A") (pinfunction "A_A") (pintype "passive"))
      (node (ref "U$49") (pin "CHOC1") (pinfunction "P0_CHOC1") (pintype "bidirectional"))
    )
    (net (code "73") (name "Net-(U$50-P0)") (class "Default")
      (node (ref "D50") (pin "A") (pinfunction "A_A") (pintype "passive"))
      (node (ref "U$50") (pin "CHOC1") (pinfunction "P0_CHOC1") (pintype "bidirectional"))
    )
    (net (code "74") (name "Net-(U$51-P0)") (class "Default")
      (node (ref "D51") (pin "A") (pinfunction "A_A") (pintype "passive"))
      (node (ref "U$51") (pin "CHOC1") (pinfunction "P0_CHOC1") (pintype "bidirectional"))
    )
    (net (code "75") (name "Net-(U$52-P0)") (class "Default")
      (node (ref "D52") (pin "A") (pinfunction "A_A") (pintype "passive"))
      (node (ref "U$52") (pin "CHOC1") (pinfunction "P0_CHOC1") (pintype "bidirectional"))
    )
    (net (code "76") (name "Net-(U$53-P0)") (class "Default")
      (node (ref "D53") (pin "A") (pinfunction "A_A") (pintype "passive"))
      (node (ref "U$53") (pin "CHOC1") (pinfunction "P0_CHOC1") (pintype "bidirectional"))
    )
    (net (code "77") (name "Net-(U$54-P0)") (class "Default")
      (node (ref "D54") (pin "A") (pinfunction "A_A") (pintype "passive"))
      (node (ref "U$54") (pin "CHOC1") (pinfunction "P0_CHOC1") (pintype "bidirectional"))
    )
    (net (code "78") (name "Net-(U$55-P0)") (class "Default")
      (node (ref "D55") (pin "A") (pinfunction "A_A") (pintype "passive"))
      (node (ref "U$55") (pin "CHOC1") (pinfunction "P0_CHOC1") (pintype "bidirectional"))
    )
    (net (code "79") (name "Net-(U$56-P0)") (class "Default")
      (node (ref "D56") (pin "A") (pinfunction "A_A") (pintype "passive"))
      (node (ref "U$56") (pin "CHOC1") (pinfunction "P0_CHOC1") (pintype "bidirectional"))
    )
    (net (code "80") (name "Net-(U$57-P0)") (class "Default")
      (node (ref "D57") (pin "A") (pinfunction "A_A") (pintype "passive"))
      (node (ref "U$57") (pin "CHOC1") (pinfunction "P0_CHOC1") (pintype "bidirectional"))
    )
    (net (code "81") (name "Net-(U$58-P0)") (class "Default")
      (node (ref "D58") (pin "A") (pinfunction "A_A") (pintype "passive"))
      (node (ref "U$58") (pin "CHOC1") (pinfunction "P0_CHOC1") (pintype "bidirectional"))
    )
    (net (code "82") (name "Net-(U$59-P0)") (class "Default")
      (node (ref "D59") (pin "A") (pinfunction "A_A") (pintype "passive"))
      (node (ref "U$59") (pin "CHOC1") (pinfunction "P0_CHOC1") (pintype "bidirectional"))
    )
    (net (code "83") (name "Net-(U$60-P0)") (class "Default")
      (node (ref "D60") (pin "A") (pinfunction "A_A") (pintype "passive"))
      (node (ref "U$60") (pin "CHOC1") (pinfunction "P0_CHOC1") (pintype "bidirectional"))
    )
    (net (code "84") (name "Net-(U$61-P0)") (class "Default")
      (node (ref "D61") (pin "A") (pinfunction "A_A") (pintype "passive"))
      (node (ref "U$61") (pin "CHOC1") (pinfunction "P0_CHOC1") (pintype "bidirectional"))
    )
    (net (code "85") (name "Net-(U$62-P0)") (class "Default")
      (node (ref "D62") (pin "A") (pinfunction "A_A") (pintype "passive"))
      (node (ref "U$62") (pin "CHOC1") (pinfunction "P0_CHOC1") (pintype "bidirectional"))
    )
    (net (code "86") (name "Net-(U$63-P0)") (class "Default")
      (node (ref "D63") (pin "A") (pinfunction "A_A") (pintype "passive"))
      (node (ref "U$63") (pin "CHOC1") (pinfunction "P0_CHOC1") (pintype "bidirectional"))
    )
    (net (code "87") (name "Net-(U$64-P0)") (class "Default")
      (node (ref "D64") (pin "A") (pinfunction "A_A") (pintype "passive"))
      (node (ref "U$64") (pin "CHOC1") (pinfunction "P0_CHOC1") (pintype "bidirectional"))
    )
    (net (code "88") (name "Net-(U$65-P0)") (class "Default")
      (node (ref "D65") (pin "A") (pinfunction "A_A") (pintype "passive"))
      (node (ref "U$65") (pin "CHOC1") (pinfunction "P0_CHOC1") (pintype "bidirectional"))
    )
    (net (code "89") (name "Net-(U$66-P0)") (class "Default")
      (node (ref "D66") (pin "A") (pinfunction "A_A") (pintype "passive"))
      (node (ref "U$66") (pin "CHOC1") (pinfunction "P0_CHOC1") (pintype "bidirectional"))
    )
    (net (code "90") (name "Net-(U$67-P0)") (class "Default")
      (node (ref "D67") (pin "A") (pinfunction "A_A") (pintype "passive"))
      (node (ref "U$67") (pin "CHOC1") (pinfunction "P0_CHOC1") (pintype "bidirectional"))
    )
    (net (code "91") (name "Net-(U$68-P0)") (class "Default")
      (node (ref "D68") (pin "A") (pinfunction "A_A") (pintype "passive"))
      (node (ref "U$68") (pin "CHOC1") (pinfunction "P0_CHOC1") (pintype "bidirectional"))
    )
    (net (code "92") (name "Net-(U$69-P0)") (class "Default")
      (node (ref "D69") (pin "A") (pinfunction "A_A") (pintype "passive"))
      (node (ref "U$69") (pin "CHOC1") (pinfunction "P0_CHOC1") (pintype "bidirectional"))
    )
    (net (code "93") (name "Net-(U$70-P0)") (class "Default")
      (node (ref "D70") (pin "A") (pinfunction "A_A") (pintype "passive"))
      (node (ref "U$70") (pin "CHOC1") (pinfunction "P0_CHOC1") (pintype "bidirectional"))
    )
    (net (code "94") (name "Net-(U$71-P0)") (class "Default")
      (node (ref "D71") (pin "A") (pinfunction "A_A") (pintype "passive"))
      (node (ref "U$71") (pin "CHOC1") (pinfunction "P0_CHOC1") (pintype "bidirectional"))
    )
    (net (code "95") (name "Net-(U$72-P0)") (class "Default")
      (node (ref "D72") (pin "A") (pinfunction "A_A") (pintype "passive"))
      (node (ref "U$72") (pin "CHOC1") (pinfunction "P0_CHOC1") (pintype "bidirectional"))
    )
    (net (code "96") (name "Net-(U$73-P0)") (class "Default")
      (node (ref "D73") (pin "A") (pinfunction "A_A") (pintype "passive"))
      (node (ref "U$73") (pin "CHOC1") (pinfunction "P0_CHOC1") (pintype "bidirectional"))
    )
    (net (code "97") (name "Net-(U$74-P0)") (class "Default")
      (node (ref "D74") (pin "A") (pinfunction "A_A") (pintype "passive"))
      (node (ref "U$74") (pin "CHOC1") (pinfunction "P0_CHOC1") (pintype "bidirectional"))
    )
    (net (code "98") (name "Net-(U$75-P0)") (class "Default")
      (node (ref "D75") (pin "A") (pinfunction "A_A") (pintype "passive"))
      (node (ref "U$75") (pin "CHOC1") (pinfunction "P0_CHOC1") (pintype "bidirectional"))
    )
    (net (code "99") (name "Net-(U$76-P0)") (class "Default")
      (node (ref "D76") (pin "A") (pinfunction "A_A") (pintype "passive"))
      (node (ref "U$76") (pin "CHOC1") (pinfunction "P0_CHOC1") (pintype "bidirectional"))
    )
    (net (code "100") (name "Net-(U$77-P0)") (class "Default")
      (node (ref "D77") (pin "A") (pinfunction "A_A") (pintype "passive"))
      (node (ref "U$77") (pin "CHOC1") (pinfunction "P0_CHOC1") (pintype "bidirectional"))
    )
    (net (code "101") (name "Net-(U$78-P0)") (class "Default")
      (node (ref "D78") (pin "A") (pinfunction "A_A") (pintype "passive"))
      (node (ref "U$78") (pin "CHOC1") (pinfunction "P0_CHOC1") (pintype "bidirectional"))
    )
    (net (code "102") (name "Net-(U$79-P0)") (class "Default")
      (node (ref "D79") (pin "A") (pinfunction "A_A") (pintype "passive"))
      (node (ref "U$79") (pin "CHOC1") (pinfunction "P0_CHOC1") (pintype "bidirectional"))
    )
    (net (code "103") (name "Net-(U$80-P0)") (class "Default")
      (node (ref "D80") (pin "A") (pinfunction "A_A") (pintype "passive"))
      (node (ref "U$80") (pin "CHOC1") (pinfunction "P0_CHOC1") (pintype "bidirectional"))
    )
    (net (code "104") (name "Net-(U$81-P0)") (class "Default")
      (node (ref "D81") (pin "A") (pinfunction "A_A") (pintype "passive"))
      (node (ref "U$81") (pin "CHOC1") (pinfunction "P0_CHOC1") (pintype "bidirectional"))
    )
    (net (code "105") (name "Net-(U$82-P0)") (class "Default")
      (node (ref "D82") (pin "A") (pinfunction "A_A") (pintype "passive"))
      (node (ref "U$82") (pin "CHOC1") (pinfunction "P0_CHOC1") (pintype "bidirectional"))
    )
    (net (code "106") (name "Net-(U$83-P0)") (class "Default")
      (node (ref "D83") (pin "A") (pinfunction "A_A") (pintype "passive"))
      (node (ref "U$83") (pin "CHOC1") (pinfunction "P0_CHOC1") (pintype "bidirectional"))
    )
    (net (code "107") (name "Net-(U$84-P0)") (class "Default")
      (node (ref "D84") (pin "A") (pinfunction "A_A") (pintype "passive"))
      (node (ref "U$84") (pin "CHOC1") (pinfunction "P0_CHOC1") (pintype "bidirectional"))
    )
    (net (code "108") (name "Net-(U$85-P0)") (class "Default")
      (node (ref "D85") (pin "A") (pinfunction "A_A") (pintype "passive"))
      (node (ref "U$85") (pin "CHOC1") (pinfunction "P0_CHOC1") (pintype "bidirectional"))
    )
    (net (code "109") (name "Net-(U$86-P0)") (class "Default")
      (node (ref "D86") (pin "A") (pinfunction "A_A") (pintype "passive"))
      (node (ref "U$86") (pin "CHOC1") (pinfunction "P0_CHOC1") (pintype "bidirectional"))
    )
    (net (code "110") (name "Net-(U$87-P0)") (class "Default")
      (node (ref "D87") (pin "A") (pinfunction "A_A") (pintype "passive"))
      (node (ref "U$87") (pin "CHOC1") (pinfunction "P0_CHOC1") (pintype "bidirectional"))
    )
    (net (code "111") (name "Net-(U$88-P0)") (class "Default")
      (node (ref "D88") (pin "A") (pinfunction "A_A") (pintype "passive"))
      (node (ref "U$88") (pin "CHOC1") (pinfunction "P0_CHOC1") (pintype "bidirectional"))
    )
    (net (code "112") (name "Net-(U$89-P0)") (class "Default")
      (node (ref "D89") (pin "A") (pinfunction "A_A") (pintype "passive"))
      (node (ref "U$89") (pin "CHOC1") (pinfunction "P0_CHOC1") (pintype "bidirectional"))
    )
    (net (code "113") (name "Net-(U$90-P0)") (class "Default")
      (node (ref "D90") (pin "A") (pinfunction "A_A") (pintype "passive"))
      (node (ref "U$90") (pin "CHOC1") (pinfunction "P0_CHOC1") (pintype "bidirectional"))
    )
    (net (code "114") (name "Net-(U$91-P0)") (class "Default")
      (node (ref "D91") (pin "A") (pinfunction "A_A") (pintype "passive"))
      (node (ref "U$91") (pin "CHOC1") (pinfunction "P0_CHOC1") (pintype "bidirectional"))
    )
    (net (code "115") (name "Net-(U$92-P0)") (class "Default")
      (node (ref "D92") (pin "A") (pinfunction "A_A") (pintype "passive"))
      (node (ref "U$92") (pin "CHOC1") (pinfunction "P0_CHOC1") (pintype "bidirectional"))
    )
    (net (code "116") (name "Net-(U$93-P0)") (class "Default")
      (node (ref "D93") (pin "A") (pinfunction "A_A") (pintype "passive"))
      (node (ref "U$93") (pin "CHOC1") (pinfunction "P0_CHOC1") (pintype "bidirectional"))
    )
    (net (code "117") (name "Net-(U$94-P0)") (class "Default")
      (node (ref "D94") (pin "A") (pinfunction "A_A") (pintype "passive"))
      (node (ref "U$94") (pin "CHOC1") (pinfunction "P0_CHOC1") (pintype "bidirectional"))
    )
    (net (code "118") (name "Net-(U$95-P0)") (class "Default")
      (node (ref "D95") (pin "A") (pinfunction "A_A") (pintype "passive"))
      (node (ref "U$95") (pin "CHOC1") (pinfunction "P0_CHOC1") (pintype "bidirectional"))
    )
    (net (code "119") (name "Net-(U$96-P0)") (class "Default")
      (node (ref "D96") (pin "A") (pinfunction "A_A") (pintype "passive"))
      (node (ref "U$96") (pin "CHOC1") (pinfunction "P0_CHOC1") (pintype "bidirectional"))
    )
    (net (code "120") (name "Net-(U$97-P0)") (class "Default")
      (node (ref "D97") (pin "A") (pinfunction "A_A") (pintype "passive"))
      (node (ref "U$97") (pin "CHOC1") (pinfunction "P0_CHOC1") (pintype "bidirectional"))
    )
    (net (code "121") (name "Net-(U$98-P0)") (class "Default")
      (node (ref "D98") (pin "A") (pinfunction "A_A") (pintype "passive"))
      (node (ref "U$98") (pin "CHOC1") (pinfunction "P0_CHOC1") (pintype "bidirectional"))
    )
    (net (code "122") (name "Net-(U$99-P0)") (class "Default")
      (node (ref "D99") (pin "A") (pinfunction "A_A") (pintype "passive"))
      (node (ref "U$99") (pin "CHOC1") (pinfunction "P0_CHOC1") (pintype "bidirectional"))
    )
    (net (code "123") (name "Net-(U$100-P0)") (class "Default")
      (node (ref "D100") (pin "A") (pinfunction "A_A") (pintype "passive"))
      (node (ref "U$100") (pin "CHOC1") (pinfunction "P0_CHOC1") (pintype "bidirectional"))
    )
    (net (code "124") (name "Net-(U$101-P0)") (class "Default")
      (node (ref "D101") (pin "A") (pinfunction "A_A") (pintype "passive"))
      (node (ref "U$101") (pin "CHOC1") (pinfunction "P0_CHOC1") (pintype "bidirectional"))
    )
    (net (code "125") (name "Net-(U$102-P0)") (class "Default")
      (node (ref "D102") (pin "A") (pinfunction "A_A") (pintype "passive"))
      (node (ref "U$102") (pin "CHOC1") (pinfunction "P0_CHOC1") (pintype "bidirectional"))
    )
    (net (code "126") (name "Net-(U$103-P0)") (class "Default")
      (node (ref "D103") (pin "A") (pinfunction "A_A") (pintype "passive"))
      (node (ref "U$103") (pin "CHOC1") (pinfunction "P0_CHOC1") (pintype "bidirectional"))
    )
    (net (code "127") (name "Net-(U$104-P0)") (class "Default")
      (node (ref "D104") (pin "A") (pinfunction "A_A") (pintype "passive"))
      (node (ref "U$104") (pin "CHOC1") (pinfunction "P0_CHOC1") (pintype "bidirectional"))
    )
    (net (code "128") (name "Net-(U$105-P0)") (class "Default")
      (node (ref "D105") (pin "A") (pinfunction "A_A") (pintype "passive"))
      (node (ref "U$105") (pin "CHOC1") (pinfunction "P0_CHOC1") (pintype "bidirectional"))
    )
    (net (code "129") (name "Net-(U$106-P0)") (class "Default")
      (node (ref "D106") (pin "A") (pinfunction "A_A") (pintype "passive"))
      (node (ref "U$106") (pin "CHOC1") (pinfunction "P0_CHOC1") (pintype "bidirectional"))
    )
    (net (code "130") (name "Net-(U$107-P0)") (class "Default")
      (node (ref "D107") (pin "A") (pinfunction "A_A") (pintype "passive"))
      (node (ref "U$107") (pin "CHOC1") (pinfunction "P0_CHOC1") (pintype "bidirectional"))
    )
    (net (code "131") (name "Net-(U$108-P0)") (class "Default")
      (node (ref "D108") (pin "A") (pinfunction "A_A") (pintype "passive"))
      (node (ref "U$108") (pin "CHOC1") (pinfunction "P0_CHOC1") (pintype "bidirectional"))
    )
    (net (code "132") (name "Net-(U$109-P0)") (class "Default")
      (node (ref "D109") (pin "A") (pinfunction "A_A") (pintype "passive"))
      (node (ref "U$109") (pin "CHOC1") (pinfunction "P0_CHOC1") (pintype "bidirectional"))
    )
    (net (code "133") (name "Net-(U$110-P0)") (class "Default")
      (node (ref "D110") (pin "A") (pinfunction "A_A") (pintype "passive"))
      (node (ref "U$110") (pin "CHOC1") (pinfunction "P0_CHOC1") (pintype "bidirectional"))
    )
    (net (code "134") (name "Net-(U$111-P0)") (class "Default")
      (node (ref "D111") (pin "A") (pinfunction "A_A") (pintype "passive"))
      (node (ref "U$111") (pin "CHOC1") (pinfunction "P0_CHOC1") (pintype "bidirectional"))
    )
    (net (code "135") (name "Net-(U$112-P0)") (class "Default")
      (node (ref "D112") (pin "A") (pinfunction "A_A") (pintype "passive"))
      (node (ref "U$112") (pin "CHOC1") (pinfunction "P0_CHOC1") (pintype "bidirectional"))
    )
    (net (code "136") (name "Net-(U$113-P0)") (class "Default")
      (node (ref "D113") (pin "A") (pinfunction "A_A") (pintype "passive"))
      (node (ref "U$113") (pin "CHOC1") (pinfunction "P0_CHOC1") (pintype "bidirectional"))
    )
    (net (code "137") (name "Net-(U$114-P0)") (class "Default")
      (node (ref "D114") (pin "A") (pinfunction "A_A") (pintype "passive"))
      (node (ref "U$114") (pin "CHOC1") (pinfunction "P0_CHOC1") (pintype "bidirectional"))
    )
    (net (code "138") (name "Net-(U$115-P0)") (class "Default")
      (node (ref "D115") (pin "A") (pinfunction "A_A") (pintype "passive"))
      (node (ref "U$115") (pin "CHOC1") (pinfunction "P0_CHOC1") (pintype "bidirectional"))
    )
    (net (code "139") (name "ROW0") (class "Default")
      (node (ref "U$123") (pin "17") (pinfunction "GP7_17") (pintype "bidirectional"))
      (node (ref "U$77") (pin "CHOC2") (pinfunction "P1_CHOC2") (pintype "bidirectional"))
      (node (ref "U$78") (pin "CHOC2") (pinfunction "P1_CHOC2") (pintype "bidirectional"))
      (node (ref "U$79") (pin "CHOC2") (pinfunction "P1_CHOC2") (pintype "bidirectional"))
      (node (ref "U$80") (pin "CHOC2") (pinfunction "P1_CHOC2") (pintype "bidirectional"))
    )
    (net (code "140") (name "ROW1") (class "Default")
      (node (ref "U$1") (pin "CHOC2") (pinfunction "P1_CHOC2") (pintype "bidirectional"))
      (node (ref "U$10") (pin "CHOC2") (pinfunction "P1_CHOC2") (pintype "bidirectional"))
      (node (ref "U$123") (pin "16") (pinfunction "GP6_16") (pintype "bidirectional"))
      (node (ref "U$2") (pin "CHOC2") (pinfunction "P1_CHOC2") (pintype "bidirectional"))
      (node (ref "U$3") (pin "CHOC2") (pinfunction "P1_CHOC2") (pintype "bidirectional"))
      (node (ref "U$4") (pin "CHOC2") (pinfunction "P1_CHOC2") (pintype "bidirectional"))
      (node (ref "U$5") (pin "CHOC2") (pinfunction "P1_CHOC2") (pintype "bidirectional"))
      (node (ref "U$6") (pin "CHOC2") (pinfunction "P1_CHOC2") (pintype "bidirectional"))
      (node (ref "U$7") (pin "CHOC2") (pinfunction "P1_CHOC2") (pintype "bidirectional"))
      (node (ref "U$71") (pin "CHOC2") (pinfunction "P1_CHOC2") (pintype "bidirectional"))
      (node (ref "U$73") (pin "CHOC2") (pinfunction "P1_CHOC2") (pintype "bidirectional"))
      (node (ref "U$8") (pin "CHOC2") (pinfunction "P1_CHOC2") (pintype "bidirectional"))
      (node (ref "U$9") (pin "CHOC2") (pinfunction "P1_CHOC2") (pintype "bidirectional"))
    )
    (net (code "141") (name "ROW2") (class "Default")
      (node (ref "U$11") (pin "CHOC2") (pinfunction "P1_CHOC2") (pintype "bidirectional"))
      (node (ref "U$115") (pin "CHOC2") (pinfunction "P1_CHOC2") (pintype "bidirectional"))
      (node (ref "U$12") (pin "CHOC2") (pinfunction "P1_CHOC2") (pintype "bidirectional"))
      (node (ref "U$123") (pin "15") (pinfunction "GP5_15") (pintype "bidirectional"))
      (node (ref "U$13") (pin "CHOC2") (pinfunction "P1_CHOC2") (pintype "bidirectional"))
      (node (ref "U$14") (pin "CHOC2") (pinfunction "P1_CHOC2") (pintype "bidirectional"))
      (node (ref "U$15") (pin "CHOC2") (pinfunction "P1_CHOC2") (pintype "bidirectional"))
      (node (ref "U$16") (pin "CHOC2") (pinfunction "P1_CHOC2") (pintype "bidirectional"))
      (node (ref "U$17") (pin "CHOC2") (pinfunction "P1_CHOC2") (pintype "bidirectional"))
      (node (ref "U$18") (pin "CHOC2") (pinfunction "P1_CHOC2") (pintype "bidirectional"))
      (node (ref "U$19") (pin "CHOC2") (pinfunction "P1_CHOC2") (pintype "bidirectional"))
      (node (ref "U$20") (pin "CHOC2") (pinfunction "P1_CHOC2") (pintype "bidirectional"))
      (node (ref "U$72") (pin "CHOC2") (pinfunction "P1_CHOC2") (pintype "bidirectional"))
      (node (ref "U$74") (pin "CHOC2") (pinfunction "P1_CHOC2") (pintype "bidirectional"))
    )
    (net (code "142") (name "ROW3") (class "Default")
      (node (ref "U$114") (pin "CHOC2") (pinfunction "P1_CHOC2") (pintype "bidirectional"))
      (node (ref "U$123") (pin "14") (pinfunction "GP4_14") (pintype "bidirectional"))
      (node (ref "U$21") (pin "CHOC2") (pinfunction "P1_CHOC2") (pintype "bidirectional"))
      (node (ref "U$22") (pin "CHOC2") (pinfunction "P1_CHOC2") (pintype "bidirectional"))
      (node (ref "U$23") (pin "CHOC2") (pinfunction "P1_CHOC2") (pintype "bidirectional"))
      (node (ref "U$24") (pin "CHOC2") (pinfunction "P1_CHOC2") (pintype "bidirectional"))
      (node (ref "U$25") (pin "CHOC2") (pinfunction "P1_CHOC2") (pintype "bidirectional"))
      (node (ref "U$26") (pin "CHOC2") (pinfunction "P1_CHOC2") (pintype "bidirectional"))
      (node (ref "U$27") (pin "CHOC2") (pinfunction "P1_CHOC2") (pintype "bidirectional"))
      (node (ref "U$28") (pin "CHOC2") (pinfunction "P1_CHOC2") (pintype "bidirectional"))
      (node (ref "U$29") (pin "CHOC2") (pinfunction "P1_CHOC2") (pintype "bidirectional"))
      (node (ref "U$30") (pin "CHOC2") (pinfunction "P1_CHOC2") (pintype "bidirectional"))
    )
    (net (code "143") (name "ROW4") (class "Default")
      (node (ref "U$113") (pin "CHOC2") (pinfunction "P1_CHOC2") (pintype "bidirectional"))
      (node (ref "U$123") (pin "13") (pinfunction "GP3_13") (pintype "bidirectional"))
      (node (ref "U$31") (pin "CHOC2") (pinfunction "P1_CHOC2") (pintype "bidirectional"))
      (node (ref "U$32") (pin "CHOC2") (pinfunction "P1_CHOC2") (pintype "bidirectional"))
      (node (ref "U$33") (pin "CHOC2") (pinfunction "P1_CHOC2") (pintype "bidirectional"))
      (node (ref "U$34") (pin "CHOC2") (pinfunction "P1_CHOC2") (pintype "bidirectional"))
      (node (ref "U$35") (pin "CHOC2") (pinfunction "P1_CHOC2") (pintype "bidirectional"))
      (node (ref "U$36") (pin "CHOC2") (pinfunction "P1_CHOC2") (pintype "bidirectional"))
      (node (ref "U$37") (pin "CHOC2") (pinfunction "P1_CHOC2") (pintype "bidirectional"))
      (node (ref "U$38") (pin "CHOC2") (pinfunction "P1_CHOC2") (pintype "bidirectional"))
      (node (ref "U$39") (pin "CHOC2") (pinfunction "P1_CHOC2") (pintype "bidirectional"))
      (node (ref "U$40") (pin "CHOC2") (pinfunction "P1_CHOC2") (pintype "bidirectional"))
    )
    (net (code "144") (name "ROW5") (class "Default")
      (node (ref "U$109") (pin "CHOC2") (pinfunction "P1_CHOC2") (pintype "bidirectional"))
      (node (ref "U$112") (pin "CHOC2") (pinfunction "P1_CHOC2") (pintype "bidirectional"))
      (node (ref "U$123") (pin "12") (pinfunction "GP2_12") (pintype "bidirectional"))
      (node (ref "U$41") (pin "CHOC2") (pinfunction "P1_CHOC2") (pintype "bidirectional"))
      (node (ref "U$42") (pin "CHOC2") (pinfunction "P1_CHOC2") (pintype "bidirectional"))
      (node (ref "U$43") (pin "CHOC2") (pinfunction "P1_CHOC2") (pintype "bidirectional"))
      (node (ref "U$44") (pin "CHOC2") (pinfunction "P1_CHOC2") (pintype "bidirectional"))
      (node (ref "U$45") (pin "CHOC2") (pinfunction "P1_CHOC2") (pintype "bidirectional"))
      (node (ref "U$46") (pin "CHOC2") (pinfunction "P1_CHOC2") (pintype "bidirectional"))
      (node (ref "U$47") (pin "CHOC2") (pinfunction "P1_CHOC2") (pintype "bidirectional"))
      (node (ref "U$48") (pin "CHOC2") (pinfunction "P1_CHOC2") (pintype "bidirectional"))
      (node (ref "U$49") (pin "CHOC2") (pinfunction "P1_CHOC2") (pintype "bidirectional"))
      (node (ref "U$50") (pin "CHOC2") (pinfunction "P1_CHOC2") (pintype "bidirectional"))
    )
    (net (code "145") (name "ROW6") (class "Default")
      (node (ref "U$108") (pin "CHOC2") (pinfunction "P1_CHOC2") (pintype "bidirectional"))
      (node (ref "U$111") (pin "CHOC2") (pinfunction "P1_CHOC2") (pintype "bidirectional"))
      (node (ref "U$123") (pin "11") (pinfunction "GP1_11") (pintype "bidirectional"))
      (node (ref "U$51") (pin "CHOC2") (pinfunction "P1_CHOC2") (pintype "bidirectional"))
      (node (ref "U$52") (pin "CHOC2") (pinfunction "P1_CHOC2") (pintype "bidirectional"))
      (node (ref "U$53") (pin "CHOC2") (pinfunction "P1_CHOC2") (pintype "bidirectional"))
      (node (ref "U$54") (pin "CHOC2") (pinfunction "P1_CHOC2") (pintype "bidirectional"))
      (node (ref "U$55") (pin "CHOC2") (pinfunction "P1_CHOC2") (pintype "bidirectional"))
      (node (ref "U$56") (pin "CHOC2") (pinfunction "P1_CHOC2") (pintype "bidirectional"))
      (node (ref "U$57") (pin "CHOC2") (pinfunction "P1_CHOC2") (pintype "bidirectional"))
      (node (ref "U$58") (pin "CHOC2") (pinfunction "P1_CHOC2") (pintype "bidirectional"))
      (node (ref "U$59") (pin "CHOC2") (pinfunction "P1_CHOC2") (pintype "bidirectional"))
      (node (ref "U$60") (pin "CHOC2") (pinfunction "P1_CHOC2") (pintype "bidirectional"))
      (node (ref "U$75") (pin "CHOC2") (pinfunction "P1_CHOC2") (pintype "bidirectional"))
      (node (ref "U$76") (pin "CHOC2") (pinfunction "P1_CHOC2") (pintype "bidirectional"))
    )
    (net (code "146") (name "ROW7") (class "Default")
      (node (ref "U$107") (pin "CHOC2") (pinfunction "P1_CHOC2") (pintype "bidirectional"))
      (node (ref "U$110") (pin "CHOC2") (pinfunction "P1_CHOC2") (pintype "bidirectional"))
      (node (ref "U$123") (pin "10") (pinfunction "GP0_10") (pintype "bidirectional"))
      (node (ref "U$61") (pin "CHOC2") (pinfunction "P1_CHOC2") (pintype "bidirectional"))
      (node (ref "U$62") (pin "CHOC2") (pinfunction "P1_CHOC2") (pintype "bidirectional"))
      (node (ref "U$63") (pin "CHOC2") (pinfunction "P1_CHOC2") (pintype "bidirectional"))
      (node (ref "U$64") (pin "CHOC2") (pinfunction "P1_CHOC2") (pintype "bidirectional"))
      (node (ref "U$65") (pin "CHOC2") (pinfunction "P1_CHOC2") (pintype "bidirectional"))
      (node (ref "U$66") (pin "CHOC2") (pinfunction "P1_CHOC2") (pintype "bidirectional"))
      (node (ref "U$67") (pin "CHOC2") (pinfunction "P1_CHOC2") (pintype "bidirectional"))
      (node (ref "U$68") (pin "CHOC2") (pinfunction "P1_CHOC2") (pintype "bidirectional"))
      (node (ref "U$69") (pin "CHOC2") (pinfunction "P1_CHOC2") (pintype "bidirectional"))
      (node (ref "U$70") (pin "CHOC2") (pinfunction "P1_CHOC2") (pintype "bidirectional"))
    )
    (net (code "147") (name "ROW8") (class "Default")
      (node (ref "U$100") (pin "CHOC2") (pinfunction "P1_CHOC2") (pintype "bidirectional"))
      (node (ref "U$105") (pin "CHOC2") (pinfunction "P1_CHOC2") (pintype "bidirectional"))
      (node (ref "U$120") (pin "17") (pinfunction "GP7_17") (pintype "bidirectional"))
      (node (ref "U$81") (pin "CHOC2") (pinfunction "P1_CHOC2") (pintype "bidirectional"))
      (node (ref "U$82") (pin "CHOC2") (pinfunction "P1_CHOC2") (pintype "bidirectional"))
      (node (ref "U$83") (pin "CHOC2") (pinfunction "P1_CHOC2") (pintype "bidirectional"))
      (node (ref "U$84") (pin "CHOC2") (pinfunction "P1_CHOC2") (pintype "bidirectional"))
      (node (ref "U$85") (pin "CHOC2") (pinfunction "P1_CHOC2") (pintype "bidirectional"))
      (node (ref "U$86") (pin "CHOC2") (pinfunction "P1_CHOC2") (pintype "bidirectional"))
      (node (ref "U$99") (pin "CHOC2") (pinfunction "P1_CHOC2") (pintype "bidirectional"))
    )
    (net (code "148") (name "ROW9") (class "Default")
      (node (ref "U$101") (pin "CHOC2") (pinfunction "P1_CHOC2") (pintype "bidirectional"))
      (node (ref "U$103") (pin "CHOC2") (pinfunction "P1_CHOC2") (pintype "bidirectional"))
      (node (ref "U$120") (pin "16") (pinfunction "GP6_16") (pintype "bidirectional"))
      (node (ref "U$87") (pin "CHOC2") (pinfunction "P1_CHOC2") (pintype "bidirectional"))
      (node (ref "U$88") (pin "CHOC2") (pinfunction "P1_CHOC2") (pintype "bidirectional"))
      (node (ref "U$89") (pin "CHOC2") (pinfunction "P1_CHOC2") (pintype "bidirectional"))
      (node (ref "U$90") (pin "CHOC2") (pinfunction "P1_CHOC2") (pintype "bidirectional"))
      (node (ref "U$91") (pin "CHOC2") (pinfunction "P1_CHOC2") (pintype "bidirectional"))
      (node (ref "U$92") (pin "CHOC2") (pinfunction "P1_CHOC2") (pintype "bidirectional"))
    )
    (net (code "149") (name "ROW10") (class "Default")
      (node (ref "U$102") (pin "CHOC2") (pinfunction "P1_CHOC2") (pintype "bidirectional"))
      (node (ref "U$104") (pin "CHOC2") (pinfunction "P1_CHOC2") (pintype "bidirectional"))
      (node (ref "U$106") (pin "CHOC2") (pinfunction "P1_CHOC2") (pintype "bidirectional"))
      (node (ref "U$120") (pin "15") (pinfunction "GP5_15") (pintype "bidirectional"))
      (node (ref "U$93") (pin "CHOC2") (pinfunction "P1_CHOC2") (pintype "bidirectional"))
      (node (ref "U$94") (pin "CHOC2") (pinfunction "P1_CHOC2") (pintype "bidirectional"))
      (node (ref "U$95") (pin "CHOC2") (pinfunction "P1_CHOC2") (pintype "bidirectional"))
      (node (ref "U$96") (pin "CHOC2") (pinfunction "P1_CHOC2") (pintype "bidirectional"))
      (node (ref "U$97") (pin "CHOC2") (pinfunction "P1_CHOC2") (pintype "bidirectional"))
      (node (ref "U$98") (pin "CHOC2") (pinfunction "P1_CHOC2") (pintype "bidirectional"))
    )
    (net (code "150") (name "SCL") (class "Default")
      (node (ref "U$120") (pin "1") (pinfunction "SCL_1") (pintype "bidirectional"))
      (node (ref "U$121") (pin "1") (pinfunction "SCL_1") (pintype "bidirectional"))
      (node (ref "U$122") (pin "1") (pinfunction "SCL_1") (pintype "bidirectional"))
      (node (ref "U$123") (pin "1") (pinfunction "SCL_1") (pintype "bidirectional"))
      (node (ref "U1") (pin "6") (pinfunction "D3_6") (pintype "bidirectional"))
    )
    (net (code "151") (name "SDA") (class "Default")
      (node (ref "U$120") (pin "2") (pinfunction "SDA_2") (pintype "bidirectional"))
      (node (ref "U$121") (pin "2") (pinfunction "SDA_2") (pintype "bidirectional"))
      (node (ref "U$122") (pin "2") (pinfunction "SDA_2") (pintype "bidirectional"))
      (node (ref "U$123") (pin "2") (pinfunction "SDA_2") (pintype "bidirectional"))
      (node (ref "U1") (pin "5") (pinfunction "D2_5") (pintype "bidirectional"))
    )
    (net (code "152") (name "unconnected-(U$120-INT-Pad8)") (class "Default")
      (node (ref "U$120") (pin "8") (pinfunction "INT_8") (pintype "bidirectional"))
    )
    (net (code "153") (name "unconnected-(U$121-INT-Pad8)") (class "Default")
      (node (ref "U$121") (pin "8") (pinfunction "INT_8") (pintype "bidirectional"))
    )
    (net (code "154") (name "unconnected-(U$122-INT-Pad8)") (class "Default")
      (node (ref "U$122") (pin "8") (pinfunction "INT_8") (pintype "bidirectional"))
    )
    (net (code "155") (name "unconnected-(U$123-INT-Pad8)") (class "Default")
      (node (ref "U$123") (pin "8") (pinfunction "INT_8") (pintype "bidirectional"))
    )
    (net (code "156") (name "unconnected-(U1-10-Pad13)") (class "Default")
      (node (ref "U1") (pin "13") (pinfunction "10_13") (pintype "bidirectional"))
    )
    (net (code "157") (name "unconnected-(U1-14-Pad15)") (class "Default")
      (node (ref "U1") (pin "15") (pinfunction "14_15") (pintype "bidirectional"))
    )
    (net (code "158") (name "unconnected-(U1-15-Pad16)") (class "Default")
      (node (ref "U1") (pin "16") (pinfunction "15_16") (pintype "bidirectional"))
    )
    (net (code "159") (name "unconnected-(U1-16-Pad14)") (class "Default")
      (node (ref "U1") (pin "14") (pinfunction "16_14") (pintype "bidirectional"))
    )
    (net (code "160") (name "unconnected-(U1-A0-Pad17)") (class "Default")
      (node (ref "U1") (pin "17") (pinfunction "A0_17") (pintype "bidirectional"))
    )
    (net (code "161") (name "unconnected-(U1-A1-Pad18)") (class "Default")
      (node (ref "U1") (pin "18") (pinfunction "A1_18") (pintype "bidirectional"))
    )
    (net (code "162") (name "unconnected-(U1-A2-Pad19)") (class "Default")
      (node (ref "U1") (pin "19") (pinfunction "A2_19") (pintype "bidirectional"))
    )
    (net (code "163") (name "unconnected-(U1-A3-Pad20)") (class "Default")
      (node (ref "U1") (pin "20") (pinfunction "A3_20") (pintype "bidirectional"))
    )
    (net (code "164") (name "unconnected-(U1-D4-Pad7)") (class "Default")
      (node (ref "U1") (pin "7") (pinfunction "D4_7") (pintype "bidirectional"))
    )
    (net (code "165") (name "unconnected-(U1-D5-Pad8)") (class "Default")
      (node (ref "U1") (pin "8") (pinfunction "D5_8") (pintype "bidirectional"))
    )
    (net (code "166") (name "unconnected-(U1-D6-Pad9)") (class "Default")
      (node (ref "U1") (pin "9") (pinfunction "D6_9") (pintype "bidirectional"))
    )
    (net (code "167") (name "unconnected-(U1-D7-Pad10)") (class "Default")
      (node (ref "U1") (pin "10") (pinfunction "D7_10") (pintype "bidirectional"))
    )
    (net (code "168") (name "unconnected-(U1-D8-Pad11)") (class "Default")
      (node (ref "U1") (pin "11") (pinfunction "D8_11") (pintype "bidirectional"))
    )
    (net (code "169") (name "unconnected-(U1-D9-Pad12)") (class "Default")
      (node (ref "U1") (pin "12") (pinfunction "D9_12") (pintype "bidirectional"))
    )
    (net (code "170") (name "unconnected-(U1-RAW-Pad24)") (class "Default")
      (node (ref "U1") (pin "24") (pinfunction "RAW_24") (pintype "bidirectional"))
    )
    (net (code "171") (name "unconnected-(U1-RESET-Pad22)") (class "Default")
      (node (ref "U1") (pin "22") (pinfunction "RESET_22") (pintype "bidirectional"))
    )
    (net (code "172") (name "unconnected-(U1-RX-Pad2)") (class "Default")
      (node (ref "U1") (pin "2") (pinfunction "RX_2") (pintype "bidirectional"))
    )
    (net (code "173") (name "unconnected-(U1-TX-Pad1)") (class "Default")
      (node (ref "U1") (pin "1") (pinfunction "TX_1") (pintype "bidirectional"))
    )
  )
)
